# Schematic.net
KiCad netlist of a schematic drawn in Altium Designer
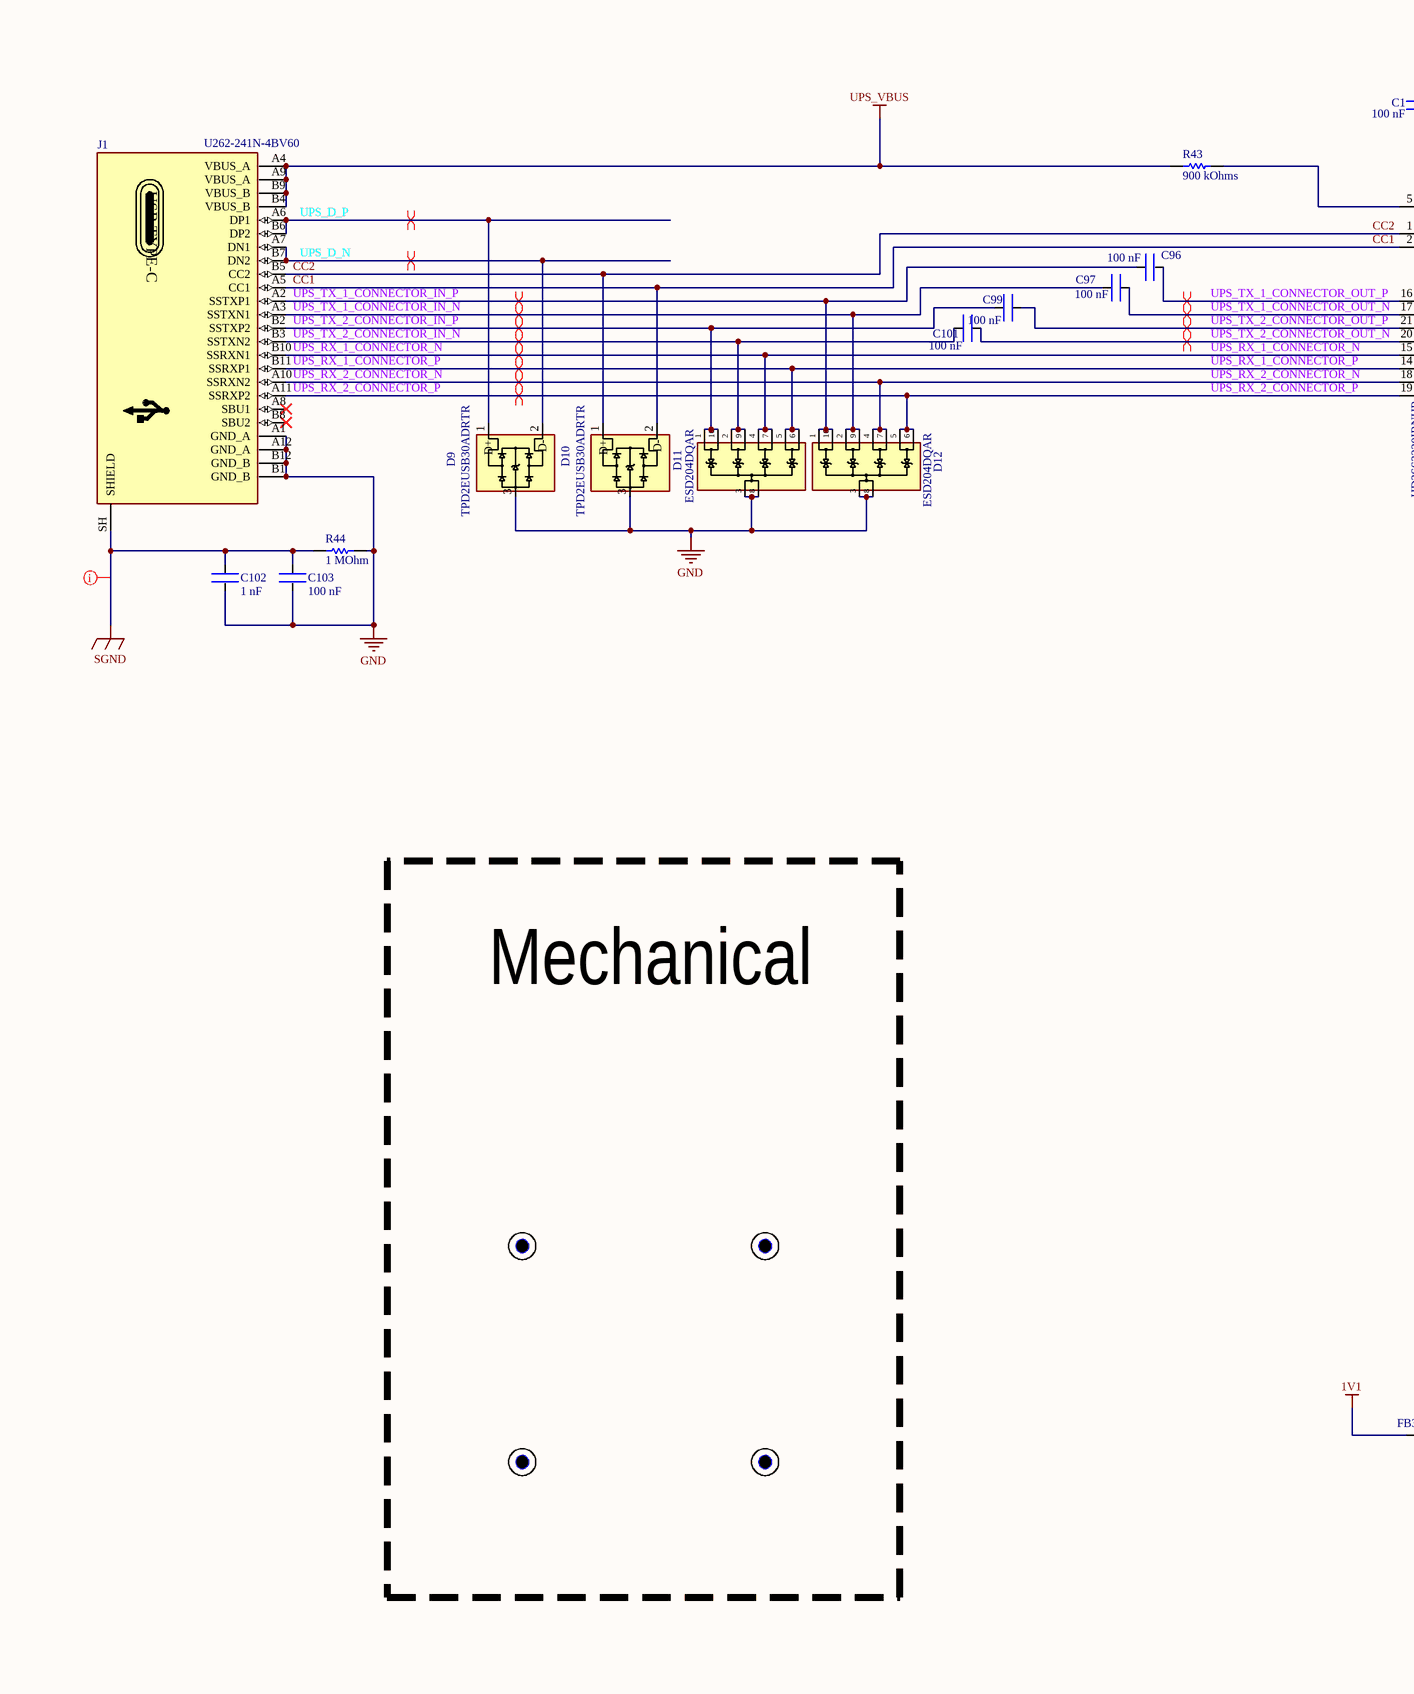
[diagram p0: Schematic.SchDoc, top left]
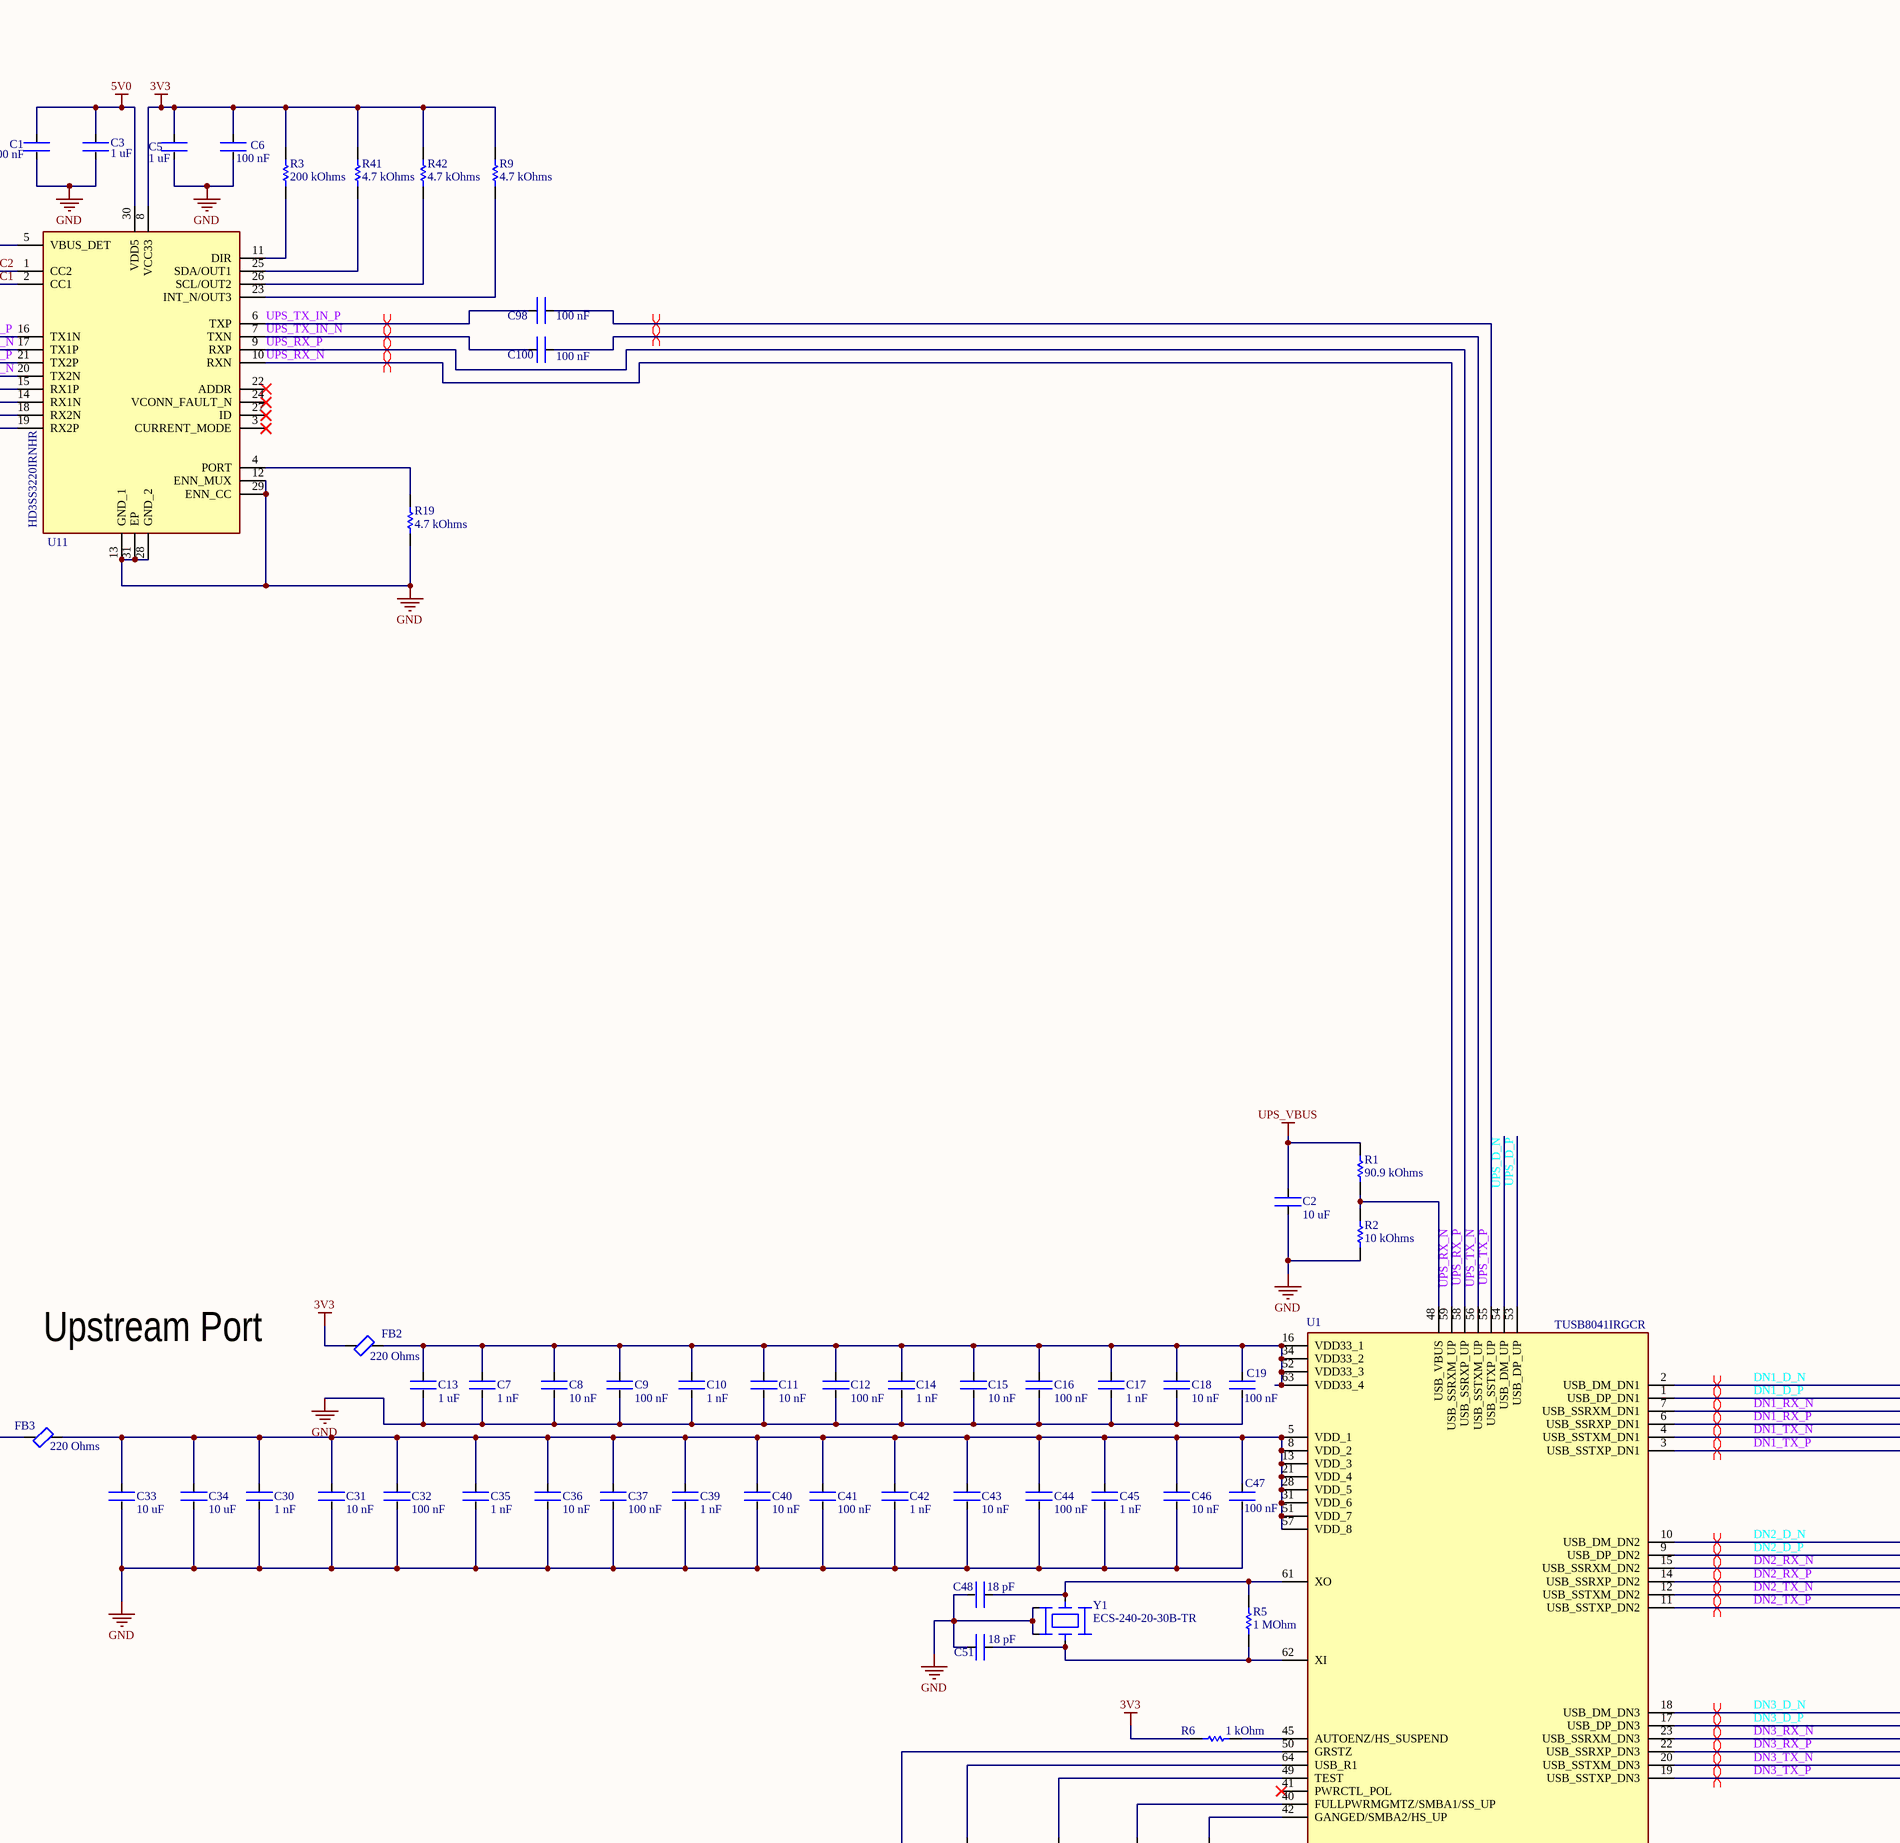
[diagram p1: Schematic.SchDoc, top middle]
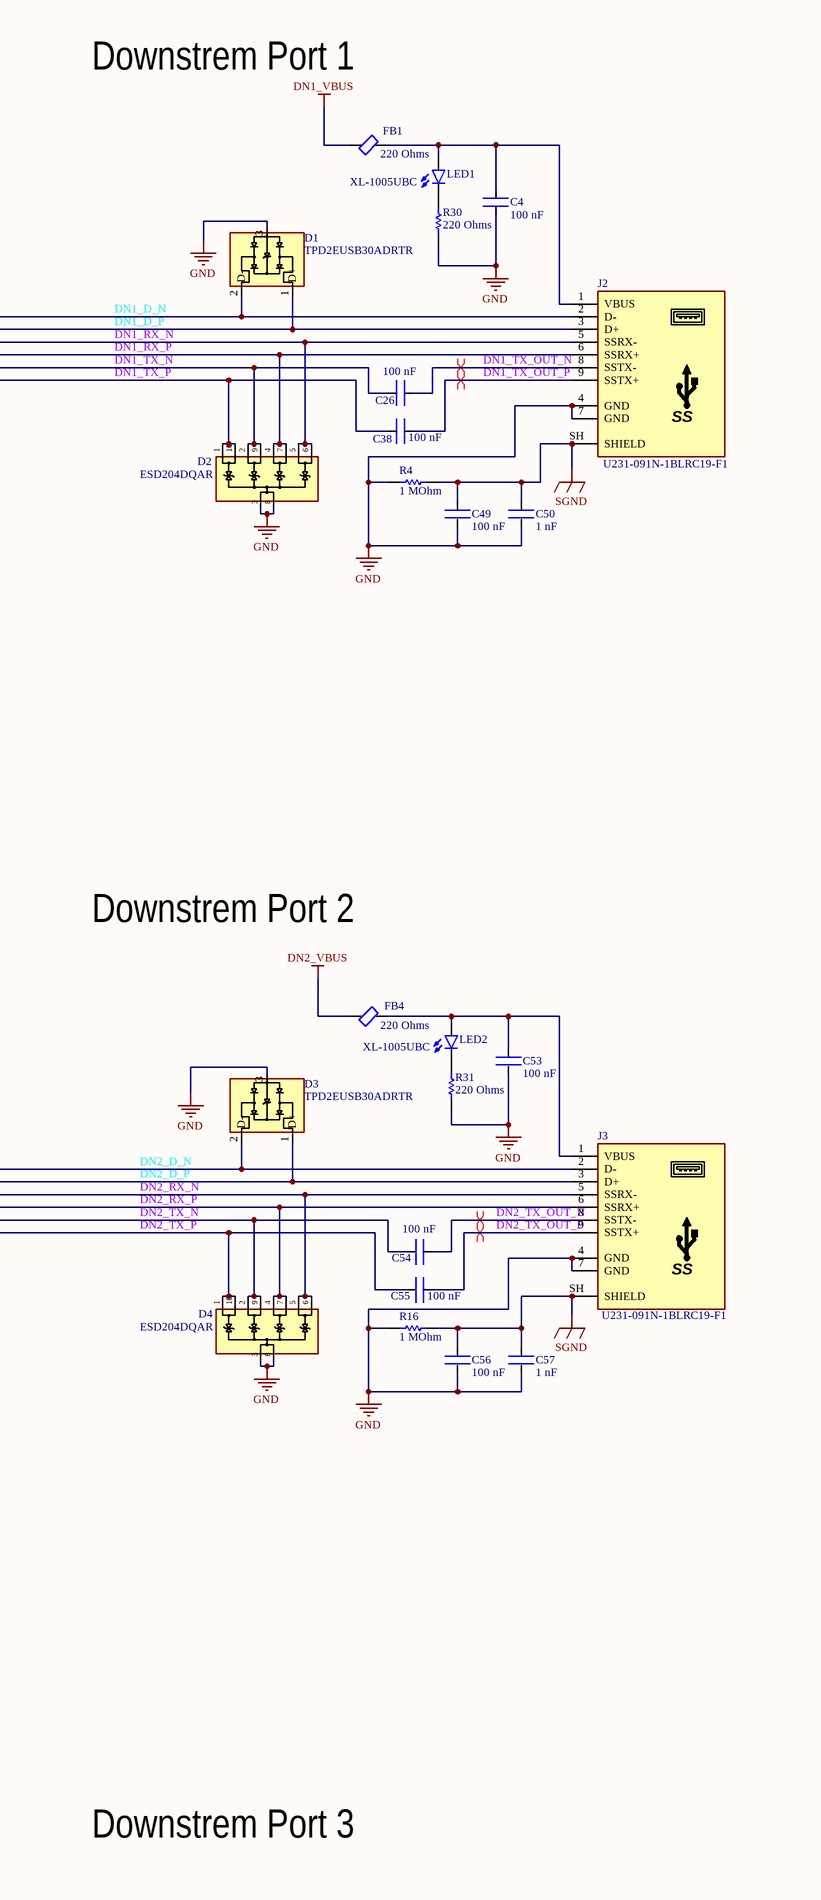
[diagram p2: Schematic.SchDoc, top right]
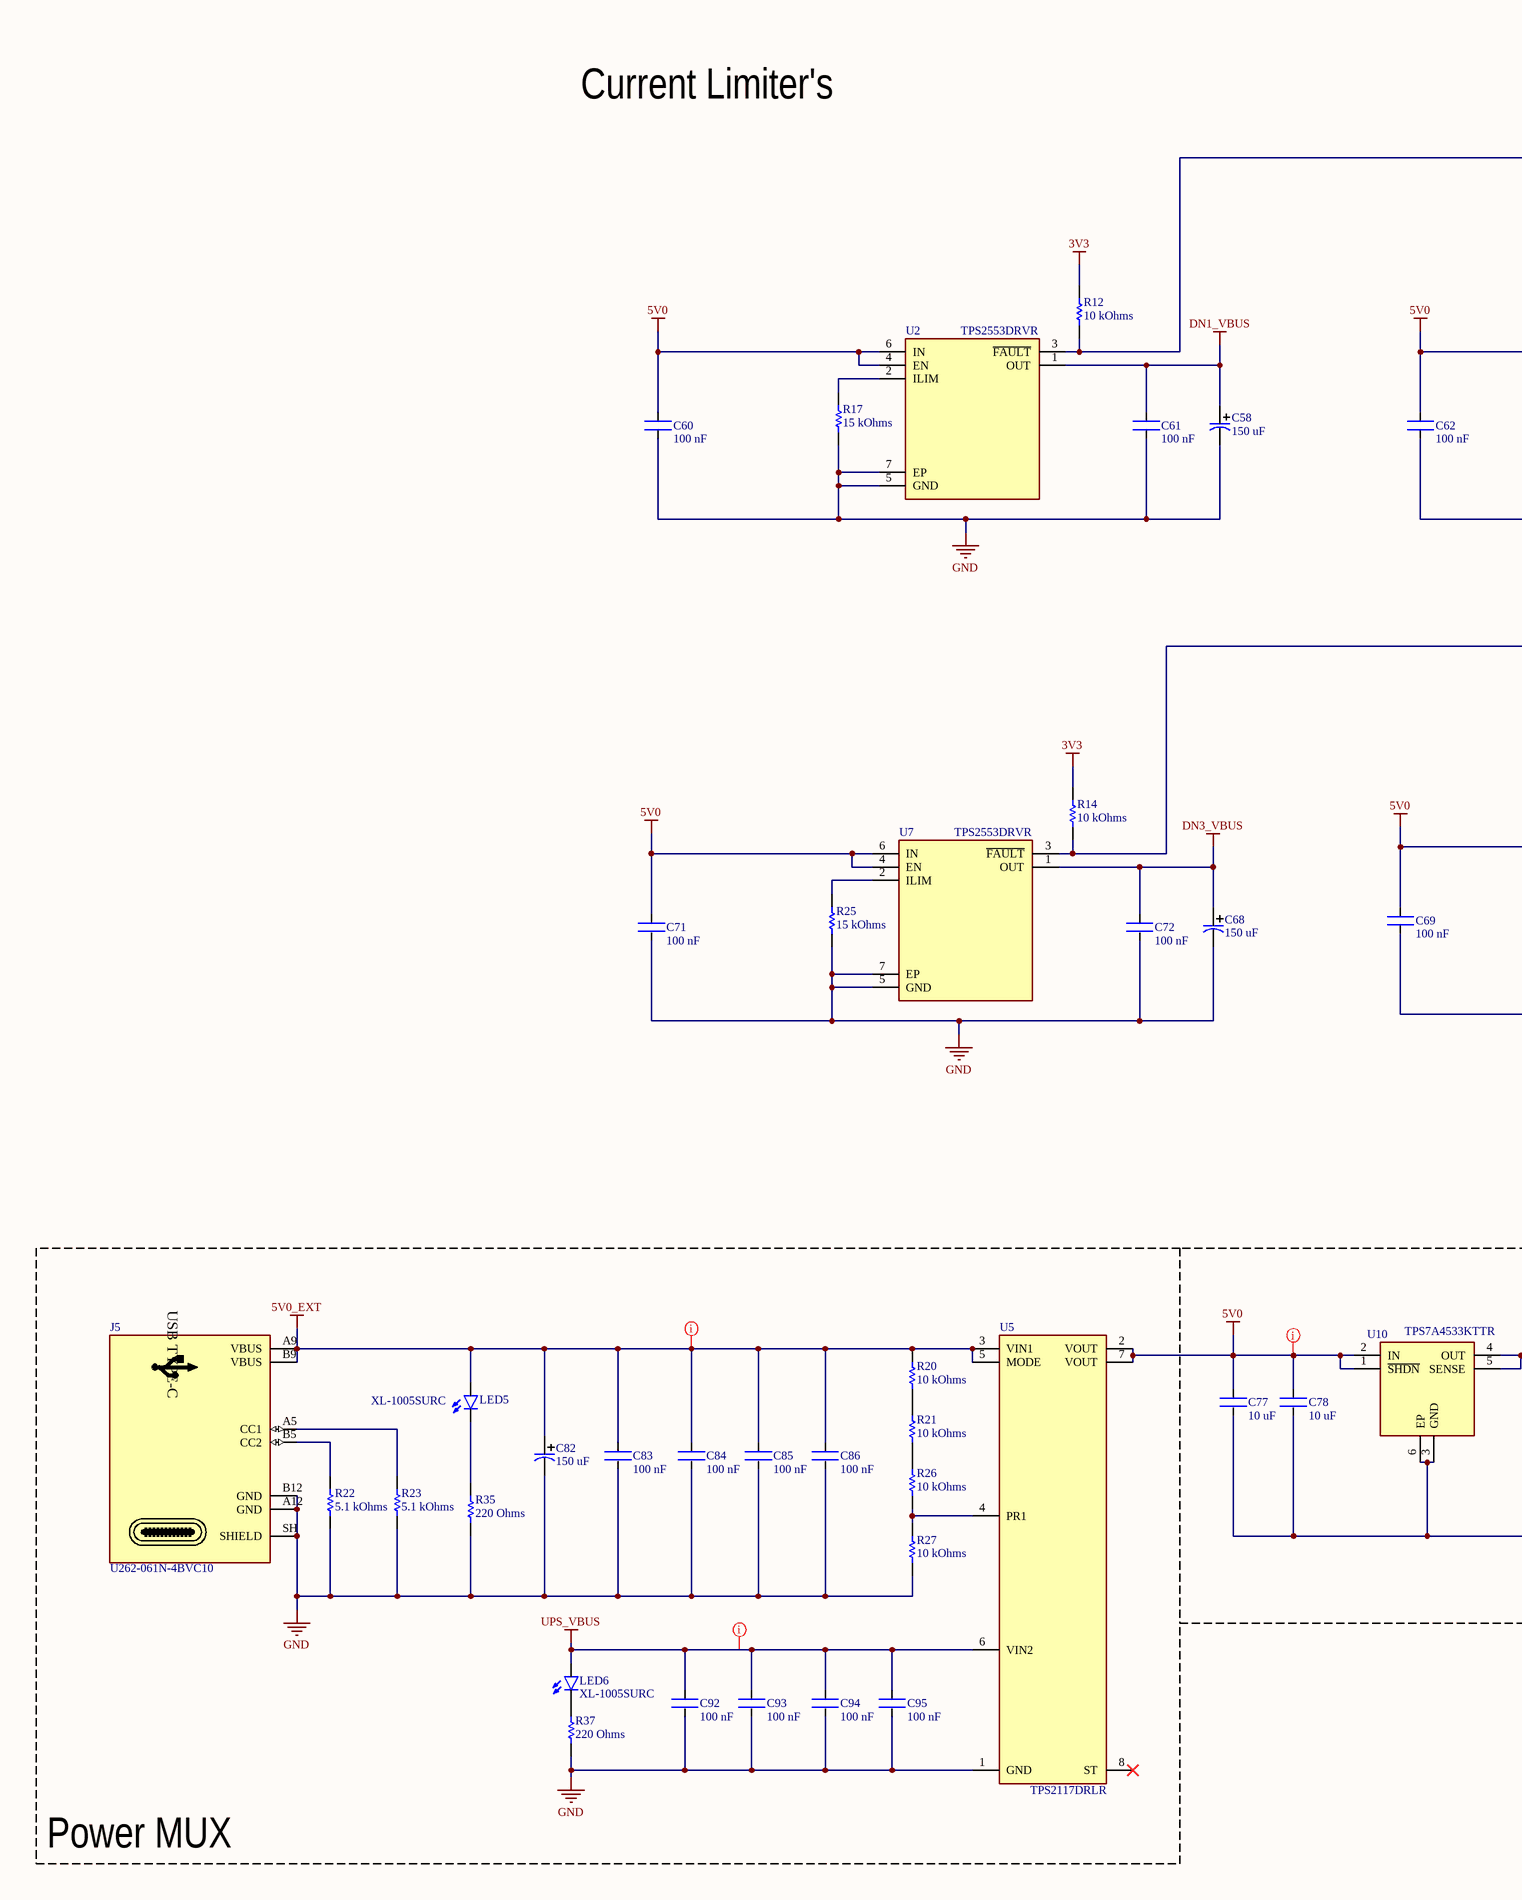
[diagram p3: Schematic.SchDoc, bottom left]
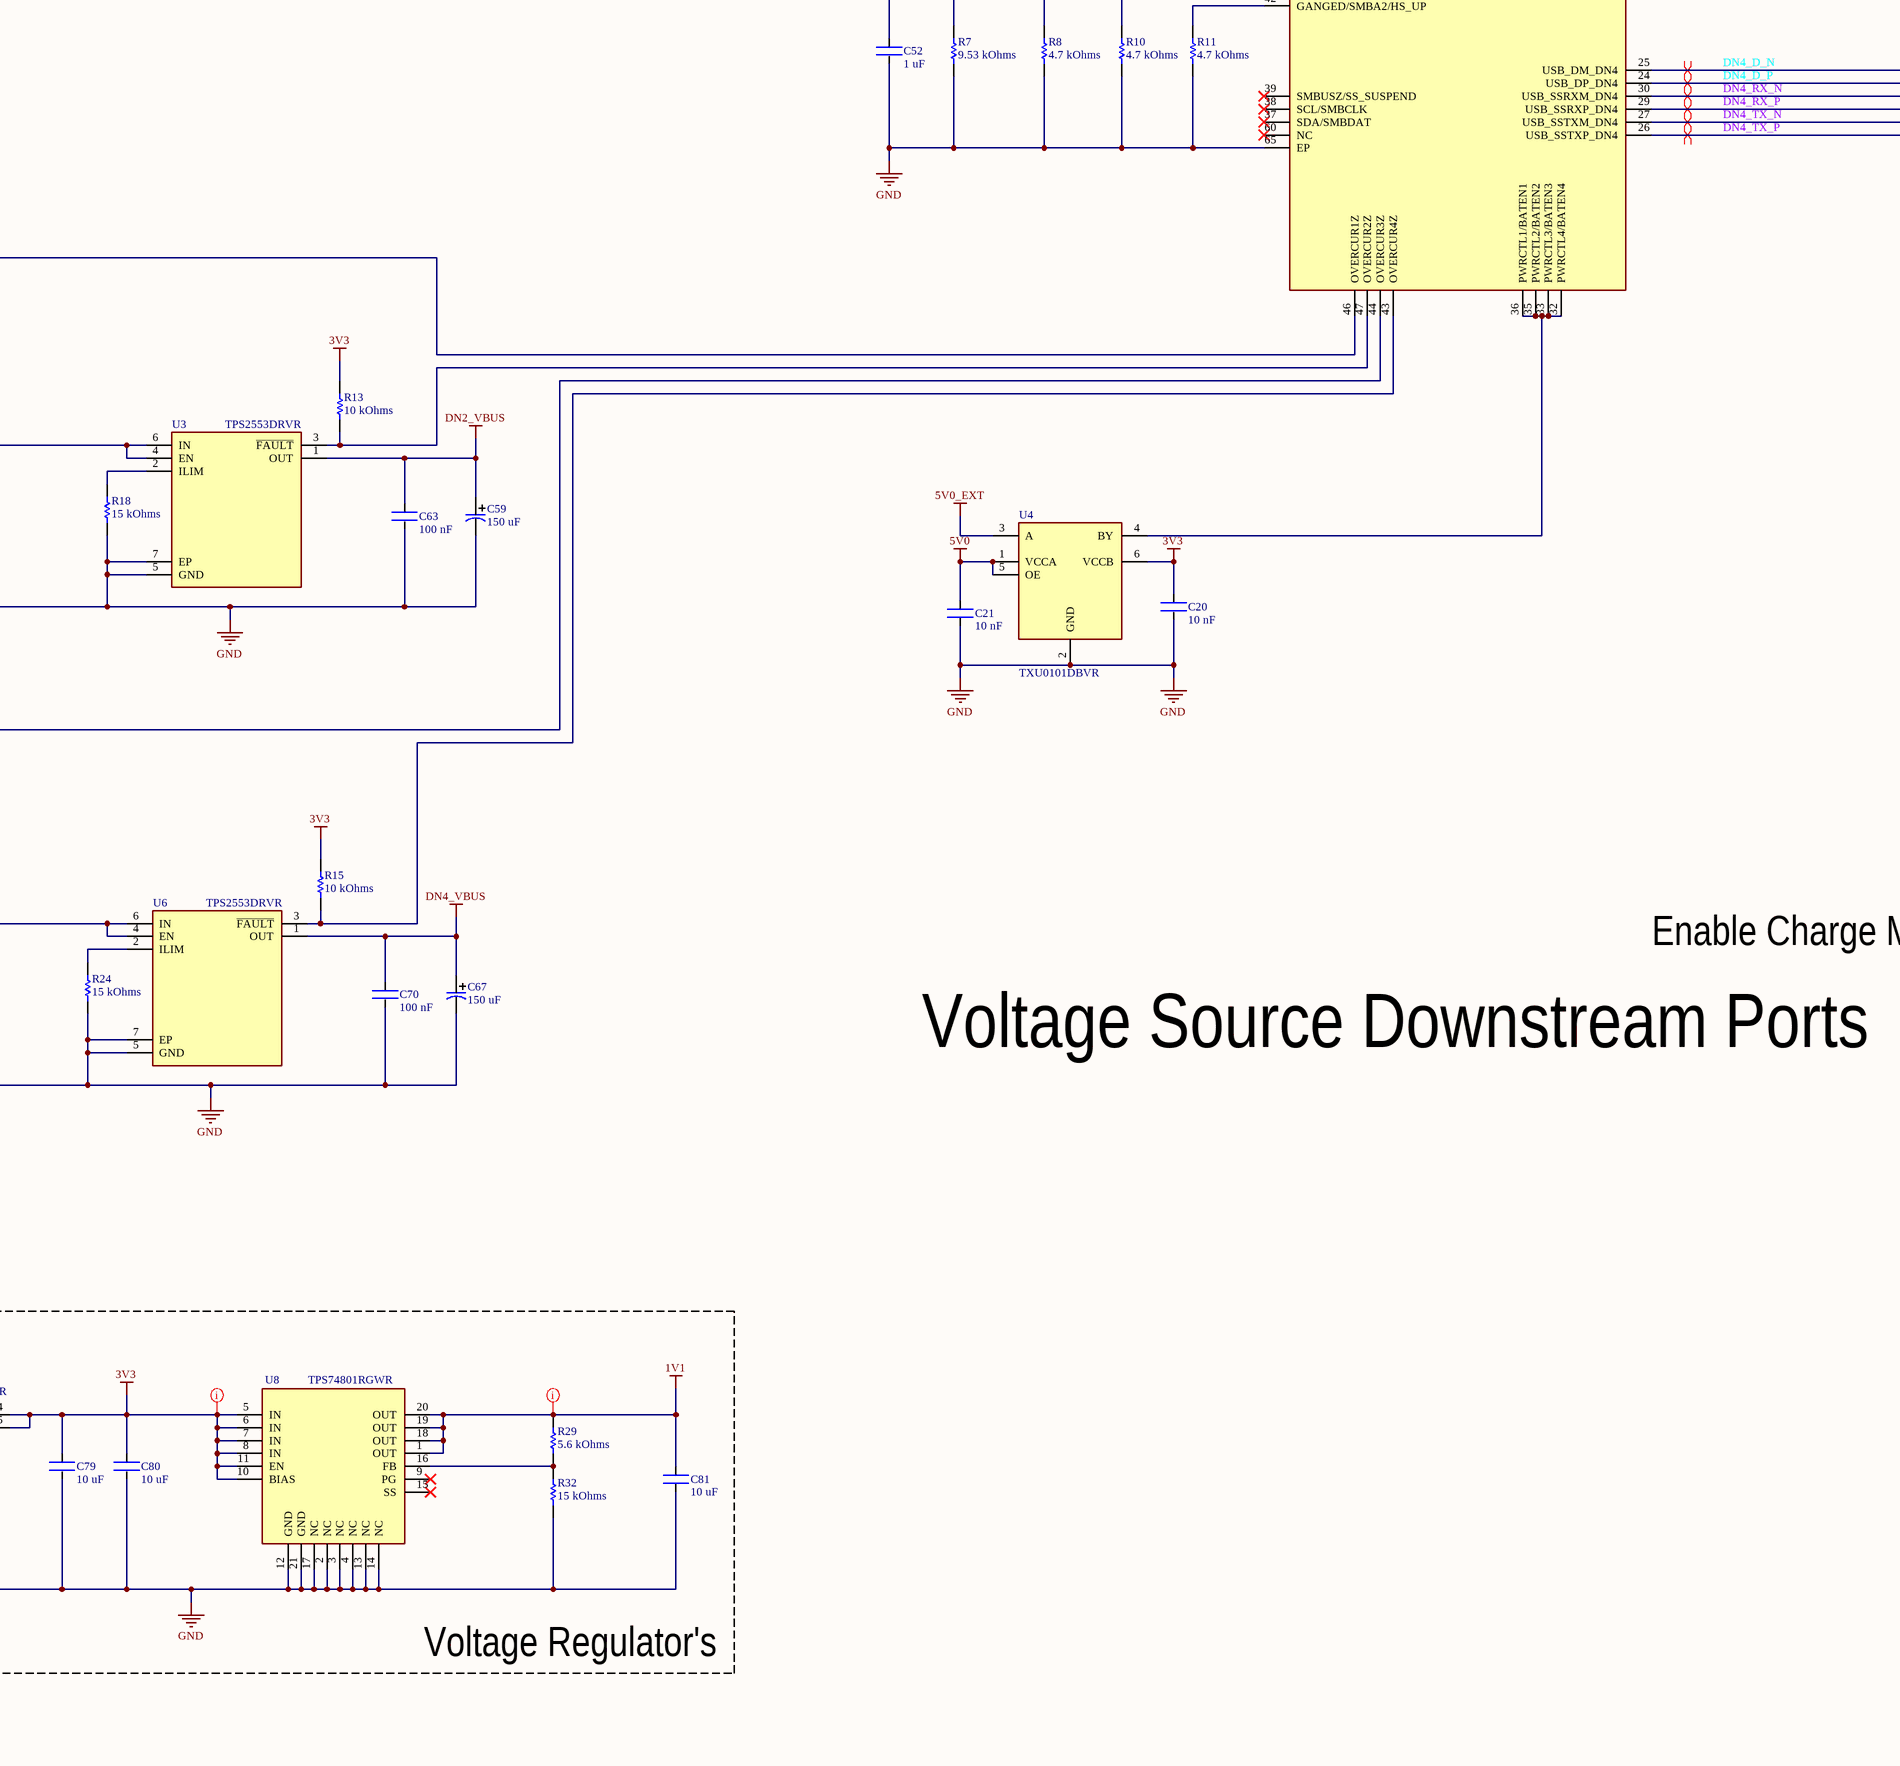
[diagram p4: Schematic.SchDoc, bottom middle]
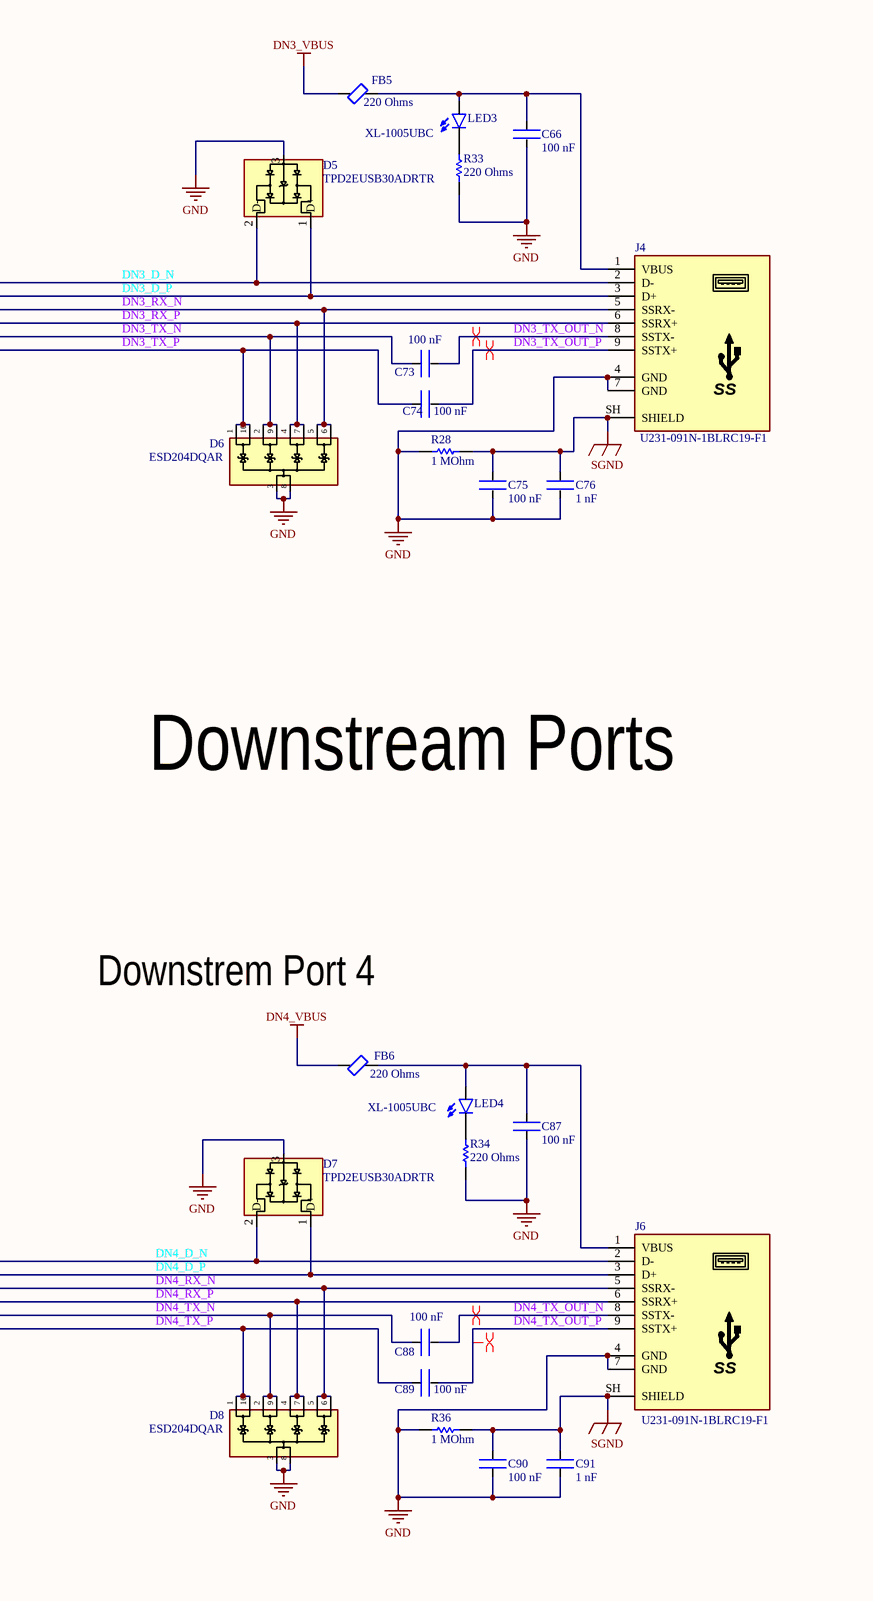
[diagram p5: Schematic.SchDoc, bottom right]

(export (version "E")
  (design (tool "Eeschema 10.0.6"))
  (components
    (comp (ref "1")
      (value "Furo")
      (footprint "FURO_M2_DIN7985")
      (description "Furo para parafuso M2")
      (fields (field (name "PART NUMBER") "FURO_M2_DIN7985"))
      (libsource (lib "MemLib") (part "Furo"))
    )
    (comp (ref "2")
      (value "Furo")
      (footprint "FURO_M2_DIN7985")
      (description "Furo para parafuso M2")
      (fields (field (name "PART NUMBER") "FURO_M2_DIN7985"))
      (libsource (lib "MemLib") (part "Furo"))
    )
    (comp (ref "3")
      (value "Furo")
      (footprint "FURO_M2_DIN7985")
      (description "Furo para parafuso M2")
      (fields (field (name "PART NUMBER") "FURO_M2_DIN7985"))
      (libsource (lib "MemLib") (part "Furo"))
    )
    (comp (ref "4")
      (value "Furo")
      (footprint "FURO_M2_DIN7985")
      (description "Furo para parafuso M2")
      (fields (field (name "PART NUMBER") "FURO_M2_DIN7985"))
      (libsource (lib "MemLib") (part "Furo"))
    )
    (comp (ref "C1")
      (value "100 nF")
      (footprint "0402")
      (description "Multilayer Ceramic Capacitors MLCC - SMD/SMT 100nF+/-10% 16V X7R 0402")
      (fields (field (name "PART NUMBER") "CL05B104KO5NNNC") (field (name "Comment") "CAPNPOL"))
      (libsource (lib "MemLib") (part "CAPNPOL"))
    )
    (comp (ref "C2")
      (value "10 uF")
      (footprint "0402")
      (description "Multilayer Ceramic Capacitors MLCC - SMD/SMT 10uF+/-20% 10V X5R 1005")
      (fields (field (name "PART NUMBER") "CL05A106MP5NUNC") (field (name "Comment") "CAPNPOL"))
      (libsource (lib "MemLib") (part "CAPNPOL"))
    )
    (comp (ref "C3")
      (value "1 uF")
      (footprint "0402")
      (description "Multilayer Ceramic Capacitors MLCC - SMD/SMT 1uF+/-10% 10V X5R 10 0402")
      (fields (field (name "PART NUMBER") "CL05A105KP5NNNC") (field (name "Comment") "CAPNPOL"))
      (libsource (lib "MemLib") (part "CAPNPOL"))
    )
    (comp (ref "C4")
      (value "100 nF")
      (footprint "0402")
      (description "Multilayer Ceramic Capacitors MLCC - SMD/SMT 100nF+/-10% 16V X7R 0402")
      (fields (field (name "PART NUMBER") "CL05B104KO5NNNC") (field (name "Comment") "CAPNPOL"))
      (libsource (lib "MemLib") (part "CAPNPOL"))
    )
    (comp (ref "C5")
      (value "1 uF")
      (footprint "0402")
      (description "Multilayer Ceramic Capacitors MLCC - SMD/SMT 1uF+/-10% 10V X5R 10 0402")
      (fields (field (name "PART NUMBER") "CL05A105KP5NNNC") (field (name "Comment") "CAPNPOL"))
      (libsource (lib "MemLib") (part "CAPNPOL"))
    )
    (comp (ref "C6")
      (value "100 nF")
      (footprint "0402")
      (description "Multilayer Ceramic Capacitors MLCC - SMD/SMT 100nF+/-10% 16V X7R 0402")
      (fields (field (name "PART NUMBER") "CL05B104KO5NNNC") (field (name "Comment") "CAPNPOL"))
      (libsource (lib "MemLib") (part "CAPNPOL"))
    )
    (comp (ref "C7")
      (value "1 nF")
      (footprint "0402")
      (description "Multilayer Ceramic Capacitors MLCC - SMD/SMT 1nF+/-10% 50V X7R 1005")
      (fields (field (name "PART NUMBER") "CL05B102KB5NNNC") (field (name "Comment") "CAPNPOL"))
      (libsource (lib "MemLib") (part "CAPNPOL"))
    )
    (comp (ref "C8")
      (value "10 nF")
      (footprint "0402")
      (description "Multilayer Ceramic Capacitors MLCC - SMD/SMT 10nF+/-10% 50V X7R 1 0402")
      (fields (field (name "PART NUMBER") "CL05B103KB5NNNC") (field (name "Comment") "CAPNPOL"))
      (libsource (lib "MemLib") (part "CAPNPOL"))
    )
    (comp (ref "C9")
      (value "100 nF")
      (footprint "0402")
      (description "Multilayer Ceramic Capacitors MLCC - SMD/SMT 100nF+/-10% 16V X7R 0402")
      (fields (field (name "PART NUMBER") "CL05B104KO5NNNC") (field (name "Comment") "CAPNPOL"))
      (libsource (lib "MemLib") (part "CAPNPOL"))
    )
    (comp (ref "C10")
      (value "1 nF")
      (footprint "0402")
      (description "Multilayer Ceramic Capacitors MLCC - SMD/SMT 1nF+/-10% 50V X7R 1005")
      (fields (field (name "PART NUMBER") "CL05B102KB5NNNC") (field (name "Comment") "CAPNPOL"))
      (libsource (lib "MemLib") (part "CAPNPOL"))
    )
    (comp (ref "C11")
      (value "10 nF")
      (footprint "0402")
      (description "Multilayer Ceramic Capacitors MLCC - SMD/SMT 10nF+/-10% 50V X7R 1 0402")
      (fields (field (name "PART NUMBER") "CL05B103KB5NNNC") (field (name "Comment") "CAPNPOL"))
      (libsource (lib "MemLib") (part "CAPNPOL"))
    )
    (comp (ref "C12")
      (value "100 nF")
      (footprint "0402")
      (description "Multilayer Ceramic Capacitors MLCC - SMD/SMT 100nF+/-10% 16V X7R 0402")
      (fields (field (name "PART NUMBER") "CL05B104KO5NNNC") (field (name "Comment") "CAPNPOL"))
      (libsource (lib "MemLib") (part "CAPNPOL"))
    )
    (comp (ref "C13")
      (value "1 uF")
      (footprint "0402")
      (description "Multilayer Ceramic Capacitors MLCC - SMD/SMT 1uF+/-10% 10V X5R 10 0402")
      (fields (field (name "PART NUMBER") "CL05A105KP5NNNC") (field (name "Comment") "CAPNPOL"))
      (libsource (lib "MemLib") (part "CAPNPOL"))
    )
    (comp (ref "C14")
      (value "1 nF")
      (footprint "0402")
      (description "Multilayer Ceramic Capacitors MLCC - SMD/SMT 1nF+/-10% 50V X7R 1005")
      (fields (field (name "PART NUMBER") "CL05B102KB5NNNC") (field (name "Comment") "CAPNPOL"))
      (libsource (lib "MemLib") (part "CAPNPOL"))
    )
    (comp (ref "C15")
      (value "10 nF")
      (footprint "0402")
      (description "Multilayer Ceramic Capacitors MLCC - SMD/SMT 10nF+/-10% 50V X7R 1 0402")
      (fields (field (name "PART NUMBER") "CL05B103KB5NNNC") (field (name "Comment") "CAPNPOL"))
      (libsource (lib "MemLib") (part "CAPNPOL"))
    )
    (comp (ref "C16")
      (value "100 nF")
      (footprint "0402")
      (description "Multilayer Ceramic Capacitors MLCC - SMD/SMT 100nF+/-10% 16V X7R 0402")
      (fields (field (name "PART NUMBER") "CL05B104KO5NNNC") (field (name "Comment") "CAPNPOL"))
      (libsource (lib "MemLib") (part "CAPNPOL"))
    )
    (comp (ref "C17")
      (value "1 nF")
      (footprint "0402")
      (description "Multilayer Ceramic Capacitors MLCC - SMD/SMT 1nF+/-10% 50V X7R 1005")
      (fields (field (name "PART NUMBER") "CL05B102KB5NNNC") (field (name "Comment") "CAPNPOL"))
      (libsource (lib "MemLib") (part "CAPNPOL"))
    )
    (comp (ref "C18")
      (value "10 nF")
      (footprint "0402")
      (description "Multilayer Ceramic Capacitors MLCC - SMD/SMT 10nF+/-10% 50V X7R 1 0402")
      (fields (field (name "PART NUMBER") "CL05B103KB5NNNC") (field (name "Comment") "CAPNPOL"))
      (libsource (lib "MemLib") (part "CAPNPOL"))
    )
    (comp (ref "C19")
      (value "100 nF")
      (footprint "0402")
      (description "Multilayer Ceramic Capacitors MLCC - SMD/SMT 100nF+/-10% 16V X7R 0402")
      (fields (field (name "PART NUMBER") "CL05B104KO5NNNC") (field (name "Comment") "CAPNPOL"))
      (libsource (lib "MemLib") (part "CAPNPOL"))
    )
    (comp (ref "C20")
      (value "10 nF")
      (footprint "0402")
      (description "Multilayer Ceramic Capacitors MLCC - SMD/SMT 10nF+/-10% 50V X7R 1 0402")
      (fields (field (name "PART NUMBER") "CL05B103KB5NNNC") (field (name "Comment") "CAPNPOL"))
      (libsource (lib "MemLib") (part "CAPNPOL"))
    )
    (comp (ref "C21")
      (value "10 nF")
      (footprint "0402")
      (description "Multilayer Ceramic Capacitors MLCC - SMD/SMT 10nF+/-10% 50V X7R 1 0402")
      (fields (field (name "PART NUMBER") "CL05B103KB5NNNC") (field (name "Comment") "CAPNPOL"))
      (libsource (lib "MemLib") (part "CAPNPOL"))
    )
    (comp (ref "C26")
      (value "100 nF")
      (footprint "0201")
      (description "Multilayer Ceramic Capacitors MLCC - SMD/SMT 0.1 uF 10 VDC 10% 0201 X5R")
      (fields (field (name "PART NUMBER") "GRM033R61A104KE15D") (field (name "Comment") "CAPNPOL"))
      (libsource (lib "MemLib") (part "CAPNPOL"))
    )
    (comp (ref "C30")
      (value "1 nF")
      (footprint "0402")
      (description "Multilayer Ceramic Capacitors MLCC - SMD/SMT 1nF+/-10% 50V X7R 1005")
      (fields (field (name "PART NUMBER") "CL05B102KB5NNNC") (field (name "Comment") "CAPNPOL"))
      (libsource (lib "MemLib") (part "CAPNPOL"))
    )
    (comp (ref "C31")
      (value "10 nF")
      (footprint "0402")
      (description "Multilayer Ceramic Capacitors MLCC - SMD/SMT 10nF+/-10% 50V X7R 1 0402")
      (fields (field (name "PART NUMBER") "CL05B103KB5NNNC") (field (name "Comment") "CAPNPOL"))
      (libsource (lib "MemLib") (part "CAPNPOL"))
    )
    (comp (ref "C32")
      (value "100 nF")
      (footprint "0402")
      (description "Multilayer Ceramic Capacitors MLCC - SMD/SMT 100nF+/-10% 16V X7R 0402")
      (fields (field (name "PART NUMBER") "CL05B104KO5NNNC") (field (name "Comment") "CAPNPOL"))
      (libsource (lib "MemLib") (part "CAPNPOL"))
    )
    (comp (ref "C33")
      (value "10 uF")
      (footprint "0402")
      (description "Multilayer Ceramic Capacitors MLCC - SMD/SMT 10uF+/-20% 10V X5R 1005")
      (fields (field (name "PART NUMBER") "CL05A106MP5NUNC") (field (name "Comment") "CAPNPOL"))
      (libsource (lib "MemLib") (part "CAPNPOL"))
    )
    (comp (ref "C34")
      (value "10 uF")
      (footprint "0402")
      (description "Multilayer Ceramic Capacitors MLCC - SMD/SMT 10uF+/-20% 10V X5R 1005")
      (fields (field (name "PART NUMBER") "CL05A106MP5NUNC") (field (name "Comment") "CAPNPOL"))
      (libsource (lib "MemLib") (part "CAPNPOL"))
    )
    (comp (ref "C35")
      (value "1 nF")
      (footprint "0402")
      (description "Multilayer Ceramic Capacitors MLCC - SMD/SMT 1nF+/-10% 50V X7R 1005")
      (fields (field (name "PART NUMBER") "CL05B102KB5NNNC") (field (name "Comment") "CAPNPOL"))
      (libsource (lib "MemLib") (part "CAPNPOL"))
    )
    (comp (ref "C36")
      (value "10 nF")
      (footprint "0402")
      (description "Multilayer Ceramic Capacitors MLCC - SMD/SMT 10nF+/-10% 50V X7R 1 0402")
      (fields (field (name "PART NUMBER") "CL05B103KB5NNNC") (field (name "Comment") "CAPNPOL"))
      (libsource (lib "MemLib") (part "CAPNPOL"))
    )
    (comp (ref "C37")
      (value "100 nF")
      (footprint "0402")
      (description "Multilayer Ceramic Capacitors MLCC - SMD/SMT 100nF+/-10% 16V X7R 0402")
      (fields (field (name "PART NUMBER") "CL05B104KO5NNNC") (field (name "Comment") "CAPNPOL"))
      (libsource (lib "MemLib") (part "CAPNPOL"))
    )
    (comp (ref "C38")
      (value "100 nF")
      (footprint "0201")
      (description "Multilayer Ceramic Capacitors MLCC - SMD/SMT 0.1 uF 10 VDC 10% 0201 X5R")
      (fields (field (name "PART NUMBER") "GRM033R61A104KE15D") (field (name "Comment") "CAPNPOL"))
      (libsource (lib "MemLib") (part "CAPNPOL"))
    )
    (comp (ref "C39")
      (value "1 nF")
      (footprint "0402")
      (description "Multilayer Ceramic Capacitors MLCC - SMD/SMT 1nF+/-10% 50V X7R 1005")
      (fields (field (name "PART NUMBER") "CL05B102KB5NNNC") (field (name "Comment") "CAPNPOL"))
      (libsource (lib "MemLib") (part "CAPNPOL"))
    )
    (comp (ref "C40")
      (value "10 nF")
      (footprint "0402")
      (description "Multilayer Ceramic Capacitors MLCC - SMD/SMT 10nF+/-10% 50V X7R 1 0402")
      (fields (field (name "PART NUMBER") "CL05B103KB5NNNC") (field (name "Comment") "CAPNPOL"))
      (libsource (lib "MemLib") (part "CAPNPOL"))
    )
    (comp (ref "C41")
      (value "100 nF")
      (footprint "0402")
      (description "Multilayer Ceramic Capacitors MLCC - SMD/SMT 100nF+/-10% 16V X7R 0402")
      (fields (field (name "PART NUMBER") "CL05B104KO5NNNC") (field (name "Comment") "CAPNPOL"))
      (libsource (lib "MemLib") (part "CAPNPOL"))
    )
    (comp (ref "C42")
      (value "1 nF")
      (footprint "0402")
      (description "Multilayer Ceramic Capacitors MLCC - SMD/SMT 1nF+/-10% 50V X7R 1005")
      (fields (field (name "PART NUMBER") "CL05B102KB5NNNC") (field (name "Comment") "CAPNPOL"))
      (libsource (lib "MemLib") (part "CAPNPOL"))
    )
    (comp (ref "C43")
      (value "10 nF")
      (footprint "0402")
      (description "Multilayer Ceramic Capacitors MLCC - SMD/SMT 10nF+/-10% 50V X7R 1 0402")
      (fields (field (name "PART NUMBER") "CL05B103KB5NNNC") (field (name "Comment") "CAPNPOL"))
      (libsource (lib "MemLib") (part "CAPNPOL"))
    )
    (comp (ref "C44")
      (value "100 nF")
      (footprint "0402")
      (description "Multilayer Ceramic Capacitors MLCC - SMD/SMT 100nF+/-10% 16V X7R 0402")
      (fields (field (name "PART NUMBER") "CL05B104KO5NNNC") (field (name "Comment") "CAPNPOL"))
      (libsource (lib "MemLib") (part "CAPNPOL"))
    )
    (comp (ref "C45")
      (value "1 nF")
      (footprint "0402")
      (description "Multilayer Ceramic Capacitors MLCC - SMD/SMT 1nF+/-10% 50V X7R 1005")
      (fields (field (name "PART NUMBER") "CL05B102KB5NNNC") (field (name "Comment") "CAPNPOL"))
      (libsource (lib "MemLib") (part "CAPNPOL"))
    )
    (comp (ref "C46")
      (value "10 nF")
      (footprint "0402")
      (description "Multilayer Ceramic Capacitors MLCC - SMD/SMT 10nF+/-10% 50V X7R 1 0402")
      (fields (field (name "PART NUMBER") "CL05B103KB5NNNC") (field (name "Comment") "CAPNPOL"))
      (libsource (lib "MemLib") (part "CAPNPOL"))
    )
    (comp (ref "C47")
      (value "100 nF")
      (footprint "0402")
      (description "Multilayer Ceramic Capacitors MLCC - SMD/SMT 100nF+/-10% 16V X7R 0402")
      (fields (field (name "PART NUMBER") "CL05B104KO5NNNC") (field (name "Comment") "CAPNPOL"))
      (libsource (lib "MemLib") (part "CAPNPOL"))
    )
    (comp (ref "C48")
      (value "18 pF")
      (footprint "0402")
      (description "Multilayer Ceramic Capacitors MLCC - SMD/SMT 50 V 18 pF C0G 0402 5%")
      (fields (field (name "PART NUMBER") "CC0402JRNPO9BN180") (field (name "Comment") "CAPNPOL"))
      (libsource (lib "MemLib") (part "CAPNPOL"))
    )
    (comp (ref "C49")
      (value "100 nF")
      (footprint "0402")
      (description "Multilayer Ceramic Capacitors MLCC - SMD/SMT 100nF+/-10% 16V X7R 0402")
      (fields (field (name "PART NUMBER") "CL05B104KO5NNNC") (field (name "Comment") "CAPNPOL"))
      (libsource (lib "MemLib") (part "CAPNPOL"))
    )
    (comp (ref "C50")
      (value "1 nF")
      (footprint "0402")
      (description "Multilayer Ceramic Capacitors MLCC - SMD/SMT 1nF+/-10% 50V X7R 1005")
      (fields (field (name "PART NUMBER") "CL05B102KB5NNNC") (field (name "Comment") "CAPNPOL"))
      (libsource (lib "MemLib") (part "CAPNPOL"))
    )
    (comp (ref "C51")
      (value "18 pF")
      (footprint "0402")
      (description "Multilayer Ceramic Capacitors MLCC - SMD/SMT 50 V 18 pF C0G 0402 5%")
      (fields (field (name "PART NUMBER") "CC0402JRNPO9BN180") (field (name "Comment") "CAPNPOL"))
      (libsource (lib "MemLib") (part "CAPNPOL"))
    )
    (comp (ref "C52")
      (value "1 uF")
      (footprint "0402")
      (description "Multilayer Ceramic Capacitors MLCC - SMD/SMT 1uF+/-10% 10V X5R 10 0402")
      (fields (field (name "PART NUMBER") "CL05A105KP5NNNC") (field (name "Comment") "CAPNPOL"))
      (libsource (lib "MemLib") (part "CAPNPOL"))
    )
    (comp (ref "C53")
      (value "100 nF")
      (footprint "0402")
      (description "Multilayer Ceramic Capacitors MLCC - SMD/SMT 100nF+/-10% 16V X7R 0402")
      (fields (field (name "PART NUMBER") "CL05B104KO5NNNC") (field (name "Comment") "CAPNPOL"))
      (libsource (lib "MemLib") (part "CAPNPOL"))
    )
    (comp (ref "C54")
      (value "100 nF")
      (footprint "0201")
      (description "Multilayer Ceramic Capacitors MLCC - SMD/SMT 0.1 uF 10 VDC 10% 0201 X5R")
      (fields (field (name "PART NUMBER") "GRM033R61A104KE15D") (field (name "Comment") "CAPNPOL"))
      (libsource (lib "MemLib") (part "CAPNPOL"))
    )
    (comp (ref "C55")
      (value "100 nF")
      (footprint "0201")
      (description "Multilayer Ceramic Capacitors MLCC - SMD/SMT 0.1 uF 10 VDC 10% 0201 X5R")
      (fields (field (name "PART NUMBER") "GRM033R61A104KE15D") (field (name "Comment") "CAPNPOL"))
      (libsource (lib "MemLib") (part "CAPNPOL"))
    )
    (comp (ref "C56")
      (value "100 nF")
      (footprint "0402")
      (description "Multilayer Ceramic Capacitors MLCC - SMD/SMT 100nF+/-10% 16V X7R 0402")
      (fields (field (name "PART NUMBER") "CL05B104KO5NNNC") (field (name "Comment") "CAPNPOL"))
      (libsource (lib "MemLib") (part "CAPNPOL"))
    )
    (comp (ref "C57")
      (value "1 nF")
      (footprint "0402")
      (description "Multilayer Ceramic Capacitors MLCC - SMD/SMT 1nF+/-10% 50V X7R 1005")
      (fields (field (name "PART NUMBER") "CL05B102KB5NNNC") (field (name "Comment") "CAPNPOL"))
      (libsource (lib "MemLib") (part "CAPNPOL"))
    )
    (comp (ref "C58")
      (value "150 uF")
      (footprint "A-3216-18")
      (description "Tantalum Capacitors - Solid SMD 4V 150uF 1206 20% ESR=800mOhms")
      (fields (field (name "PART NUMBER") "T490A157M004ATE800") (field (name "Comment") "CAPPOL"))
      (libsource (lib "MemLib") (part "CAPPOL"))
    )
    (comp (ref "C59")
      (value "150 uF")
      (footprint "A-3216-18")
      (description "Tantalum Capacitors - Solid SMD 4V 150uF 1206 20% ESR=800mOhms")
      (fields (field (name "PART NUMBER") "T490A157M004ATE800") (field (name "Comment") "CAPPOL"))
      (libsource (lib "MemLib") (part "CAPPOL"))
    )
    (comp (ref "C60")
      (value "100 nF")
      (footprint "0402")
      (description "Multilayer Ceramic Capacitors MLCC - SMD/SMT 100nF+/-10% 16V X7R 0402")
      (fields (field (name "PART NUMBER") "CL05B104KO5NNNC") (field (name "Comment") "CAPNPOL"))
      (libsource (lib "MemLib") (part "CAPNPOL"))
    )
    (comp (ref "C61")
      (value "100 nF")
      (footprint "0402")
      (description "Multilayer Ceramic Capacitors MLCC - SMD/SMT 100nF+/-10% 16V X7R 0402")
      (fields (field (name "PART NUMBER") "CL05B104KO5NNNC") (field (name "Comment") "CAPNPOL"))
      (libsource (lib "MemLib") (part "CAPNPOL"))
    )
    (comp (ref "C62")
      (value "100 nF")
      (footprint "0402")
      (description "Multilayer Ceramic Capacitors MLCC - SMD/SMT 100nF+/-10% 16V X7R 0402")
      (fields (field (name "PART NUMBER") "CL05B104KO5NNNC") (field (name "Comment") "CAPNPOL"))
      (libsource (lib "MemLib") (part "CAPNPOL"))
    )
    (comp (ref "C63")
      (value "100 nF")
      (footprint "0402")
      (description "Multilayer Ceramic Capacitors MLCC - SMD/SMT 100nF+/-10% 16V X7R 0402")
      (fields (field (name "PART NUMBER") "CL05B104KO5NNNC") (field (name "Comment") "CAPNPOL"))
      (libsource (lib "MemLib") (part "CAPNPOL"))
    )
    (comp (ref "C66")
      (value "100 nF")
      (footprint "0402")
      (description "Multilayer Ceramic Capacitors MLCC - SMD/SMT 100nF+/-10% 16V X7R 0402")
      (fields (field (name "PART NUMBER") "CL05B104KO5NNNC") (field (name "Comment") "CAPNPOL"))
      (libsource (lib "MemLib") (part "CAPNPOL"))
    )
    (comp (ref "C67")
      (value "150 uF")
      (footprint "A-3216-18")
      (description "Tantalum Capacitors - Solid SMD 4V 150uF 1206 20% ESR=800mOhms")
      (fields (field (name "PART NUMBER") "T490A157M004ATE800") (field (name "Comment") "CAPPOL"))
      (libsource (lib "MemLib") (part "CAPPOL"))
    )
    (comp (ref "C68")
      (value "150 uF")
      (footprint "A-3216-18")
      (description "Tantalum Capacitors - Solid SMD 4V 150uF 1206 20% ESR=800mOhms")
      (fields (field (name "PART NUMBER") "T490A157M004ATE800") (field (name "Comment") "CAPPOL"))
      (libsource (lib "MemLib") (part "CAPPOL"))
    )
    (comp (ref "C69")
      (value "100 nF")
      (footprint "0402")
      (description "Multilayer Ceramic Capacitors MLCC - SMD/SMT 100nF+/-10% 16V X7R 0402")
      (fields (field (name "PART NUMBER") "CL05B104KO5NNNC") (field (name "Comment") "CAPNPOL"))
      (libsource (lib "MemLib") (part "CAPNPOL"))
    )
    (comp (ref "C70")
      (value "100 nF")
      (footprint "0402")
      (description "Multilayer Ceramic Capacitors MLCC - SMD/SMT 100nF+/-10% 16V X7R 0402")
      (fields (field (name "PART NUMBER") "CL05B104KO5NNNC") (field (name "Comment") "CAPNPOL"))
      (libsource (lib "MemLib") (part "CAPNPOL"))
    )
    (comp (ref "C71")
      (value "100 nF")
      (footprint "0402")
      (description "Multilayer Ceramic Capacitors MLCC - SMD/SMT 100nF+/-10% 16V X7R 0402")
      (fields (field (name "PART NUMBER") "CL05B104KO5NNNC") (field (name "Comment") "CAPNPOL"))
      (libsource (lib "MemLib") (part "CAPNPOL"))
    )
    (comp (ref "C72")
      (value "100 nF")
      (footprint "0402")
      (description "Multilayer Ceramic Capacitors MLCC - SMD/SMT 100nF+/-10% 16V X7R 0402")
      (fields (field (name "PART NUMBER") "CL05B104KO5NNNC") (field (name "Comment") "CAPNPOL"))
      (libsource (lib "MemLib") (part "CAPNPOL"))
    )
    (comp (ref "C73")
      (value "100 nF")
      (footprint "0201")
      (description "Multilayer Ceramic Capacitors MLCC - SMD/SMT 0.1 uF 10 VDC 10% 0201 X5R")
      (fields (field (name "PART NUMBER") "GRM033R61A104KE15D") (field (name "Comment") "CAPNPOL"))
      (libsource (lib "MemLib") (part "CAPNPOL"))
    )
    (comp (ref "C74")
      (value "100 nF")
      (footprint "0201")
      (description "Multilayer Ceramic Capacitors MLCC - SMD/SMT 0.1 uF 10 VDC 10% 0201 X5R")
      (fields (field (name "PART NUMBER") "GRM033R61A104KE15D") (field (name "Comment") "CAPNPOL"))
      (libsource (lib "MemLib") (part "CAPNPOL"))
    )
    (comp (ref "C75")
      (value "100 nF")
      (footprint "0402")
      (description "Multilayer Ceramic Capacitors MLCC - SMD/SMT 100nF+/-10% 16V X7R 0402")
      (fields (field (name "PART NUMBER") "CL05B104KO5NNNC") (field (name "Comment") "CAPNPOL"))
      (libsource (lib "MemLib") (part "CAPNPOL"))
    )
    (comp (ref "C76")
      (value "1 nF")
      (footprint "0402")
      (description "Multilayer Ceramic Capacitors MLCC - SMD/SMT 1nF+/-10% 50V X7R 1005")
      (fields (field (name "PART NUMBER") "CL05B102KB5NNNC") (field (name "Comment") "CAPNPOL"))
      (libsource (lib "MemLib") (part "CAPNPOL"))
    )
    (comp (ref "C77")
      (value "10 uF")
      (footprint "0402")
      (description "Multilayer Ceramic Capacitors MLCC - SMD/SMT 10uF+/-20% 10V X5R 1005")
      (fields (field (name "PART NUMBER") "CL05A106MP5NUNC") (field (name "Comment") "CAPNPOL"))
      (libsource (lib "MemLib") (part "CAPNPOL"))
    )
    (comp (ref "C78")
      (value "10 uF")
      (footprint "0402")
      (description "Multilayer Ceramic Capacitors MLCC - SMD/SMT 10uF+/-20% 10V X5R 1005")
      (fields (field (name "PART NUMBER") "CL05A106MP5NUNC") (field (name "Comment") "CAPNPOL"))
      (libsource (lib "MemLib") (part "CAPNPOL"))
    )
    (comp (ref "C79")
      (value "10 uF")
      (footprint "0402")
      (description "Multilayer Ceramic Capacitors MLCC - SMD/SMT 10uF+/-20% 10V X5R 1005")
      (fields (field (name "PART NUMBER") "CL05A106MP5NUNC") (field (name "Comment") "CAPNPOL"))
      (libsource (lib "MemLib") (part "CAPNPOL"))
    )
    (comp (ref "C80")
      (value "10 uF")
      (footprint "0402")
      (description "Multilayer Ceramic Capacitors MLCC - SMD/SMT 10uF+/-20% 10V X5R 1005")
      (fields (field (name "PART NUMBER") "CL05A106MP5NUNC") (field (name "Comment") "CAPNPOL"))
      (libsource (lib "MemLib") (part "CAPNPOL"))
    )
    (comp (ref "C81")
      (value "10 uF")
      (footprint "0402")
      (description "Multilayer Ceramic Capacitors MLCC - SMD/SMT 10uF+/-20% 10V X5R 1005")
      (fields (field (name "PART NUMBER") "CL05A106MP5NUNC") (field (name "Comment") "CAPNPOL"))
      (libsource (lib "MemLib") (part "CAPNPOL"))
    )
    (comp (ref "C82")
      (value "150 uF")
      (footprint "A-3216-18")
      (description "Tantalum Capacitors - Solid SMD 4V 150uF 1206 20% ESR=800mOhms")
      (fields (field (name "PART NUMBER") "T490A157M004ATE800") (field (name "Comment") "CAPPOL"))
      (libsource (lib "MemLib") (part "CAPPOL"))
    )
    (comp (ref "C83")
      (value "100 nF")
      (footprint "0402")
      (description "Multilayer Ceramic Capacitors MLCC - SMD/SMT 100nF+/-10% 16V X7R 0402")
      (fields (field (name "PART NUMBER") "CL05B104KO5NNNC") (field (name "Comment") "CAPNPOL"))
      (libsource (lib "MemLib") (part "CAPNPOL"))
    )
    (comp (ref "C84")
      (value "100 nF")
      (footprint "0402")
      (description "Multilayer Ceramic Capacitors MLCC - SMD/SMT 100nF+/-10% 16V X7R 0402")
      (fields (field (name "PART NUMBER") "CL05B104KO5NNNC") (field (name "Comment") "CAPNPOL"))
      (libsource (lib "MemLib") (part "CAPNPOL"))
    )
    (comp (ref "C85")
      (value "100 nF")
      (footprint "0402")
      (description "Multilayer Ceramic Capacitors MLCC - SMD/SMT 100nF+/-10% 16V X7R 0402")
      (fields (field (name "PART NUMBER") "CL05B104KO5NNNC") (field (name "Comment") "CAPNPOL"))
      (libsource (lib "MemLib") (part "CAPNPOL"))
    )
    (comp (ref "C86")
      (value "100 nF")
      (footprint "0402")
      (description "Multilayer Ceramic Capacitors MLCC - SMD/SMT 100nF+/-10% 16V X7R 0402")
      (fields (field (name "PART NUMBER") "CL05B104KO5NNNC") (field (name "Comment") "CAPNPOL"))
      (libsource (lib "MemLib") (part "CAPNPOL"))
    )
    (comp (ref "C87")
      (value "100 nF")
      (footprint "0402")
      (description "Multilayer Ceramic Capacitors MLCC - SMD/SMT 100nF+/-10% 16V X7R 0402")
      (fields (field (name "PART NUMBER") "CL05B104KO5NNNC") (field (name "Comment") "CAPNPOL"))
      (libsource (lib "MemLib") (part "CAPNPOL"))
    )
    (comp (ref "C88")
      (value "100 nF")
      (footprint "0201")
      (description "Multilayer Ceramic Capacitors MLCC - SMD/SMT 0.1 uF 10 VDC 10% 0201 X5R")
      (fields (field (name "PART NUMBER") "GRM033R61A104KE15D") (field (name "Comment") "CAPNPOL"))
      (libsource (lib "MemLib") (part "CAPNPOL"))
    )
    (comp (ref "C89")
      (value "100 nF")
      (footprint "0201")
      (description "Multilayer Ceramic Capacitors MLCC - SMD/SMT 0.1 uF 10 VDC 10% 0201 X5R")
      (fields (field (name "PART NUMBER") "GRM033R61A104KE15D") (field (name "Comment") "CAPNPOL"))
      (libsource (lib "MemLib") (part "CAPNPOL"))
    )
    (comp (ref "C90")
      (value "100 nF")
      (footprint "0402")
      (description "Multilayer Ceramic Capacitors MLCC - SMD/SMT 100nF+/-10% 16V X7R 0402")
      (fields (field (name "PART NUMBER") "CL05B104KO5NNNC") (field (name "Comment") "CAPNPOL"))
      (libsource (lib "MemLib") (part "CAPNPOL"))
    )
    (comp (ref "C91")
      (value "1 nF")
      (footprint "0402")
      (description "Multilayer Ceramic Capacitors MLCC - SMD/SMT 1nF+/-10% 50V X7R 1005")
      (fields (field (name "PART NUMBER") "CL05B102KB5NNNC") (field (name "Comment") "CAPNPOL"))
      (libsource (lib "MemLib") (part "CAPNPOL"))
    )
    (comp (ref "C92")
      (value "100 nF")
      (footprint "0402")
      (description "Multilayer Ceramic Capacitors MLCC - SMD/SMT 100nF+/-10% 16V X7R 0402")
      (fields (field (name "PART NUMBER") "CL05B104KO5NNNC") (field (name "Comment") "CAPNPOL"))
      (libsource (lib "MemLib") (part "CAPNPOL"))
    )
    (comp (ref "C93")
      (value "100 nF")
      (footprint "0402")
      (description "Multilayer Ceramic Capacitors MLCC - SMD/SMT 100nF+/-10% 16V X7R 0402")
      (fields (field (name "PART NUMBER") "CL05B104KO5NNNC") (field (name "Comment") "CAPNPOL"))
      (libsource (lib "MemLib") (part "CAPNPOL"))
    )
    (comp (ref "C94")
      (value "100 nF")
      (footprint "0402")
      (description "Multilayer Ceramic Capacitors MLCC - SMD/SMT 100nF+/-10% 16V X7R 0402")
      (fields (field (name "PART NUMBER") "CL05B104KO5NNNC") (field (name "Comment") "CAPNPOL"))
      (libsource (lib "MemLib") (part "CAPNPOL"))
    )
    (comp (ref "C95")
      (value "100 nF")
      (footprint "0402")
      (description "Multilayer Ceramic Capacitors MLCC - SMD/SMT 100nF+/-10% 16V X7R 0402")
      (fields (field (name "PART NUMBER") "CL05B104KO5NNNC") (field (name "Comment") "CAPNPOL"))
      (libsource (lib "MemLib") (part "CAPNPOL"))
    )
    (comp (ref "C96")
      (value "100 nF")
      (footprint "0201")
      (description "Multilayer Ceramic Capacitors MLCC - SMD/SMT 0.1 uF 10 VDC 10% 0201 X5R")
      (fields (field (name "PART NUMBER") "GRM033R61A104KE15D") (field (name "Comment") "CAPNPOL"))
      (libsource (lib "MemLib") (part "CAPNPOL"))
    )
    (comp (ref "C97")
      (value "100 nF")
      (footprint "0201")
      (description "Multilayer Ceramic Capacitors MLCC - SMD/SMT 0.1 uF 10 VDC 10% 0201 X5R")
      (fields (field (name "PART NUMBER") "GRM033R61A104KE15D") (field (name "Comment") "CAPNPOL"))
      (libsource (lib "MemLib") (part "CAPNPOL"))
    )
    (comp (ref "C98")
      (value "100 nF")
      (footprint "0201")
      (description "Multilayer Ceramic Capacitors MLCC - SMD/SMT 0.1 uF 10 VDC 10% 0201 X5R")
      (fields (field (name "PART NUMBER") "GRM033R61A104KE15D") (field (name "Comment") "CAPNPOL"))
      (libsource (lib "MemLib") (part "CAPNPOL"))
    )
    (comp (ref "C99")
      (value "100 nF")
      (footprint "0201")
      (description "Multilayer Ceramic Capacitors MLCC - SMD/SMT 0.1 uF 10 VDC 10% 0201 X5R")
      (fields (field (name "PART NUMBER") "GRM033R61A104KE15D") (field (name "Comment") "CAPNPOL"))
      (libsource (lib "MemLib") (part "CAPNPOL"))
    )
    (comp (ref "C100")
      (value "100 nF")
      (footprint "0201")
      (description "Multilayer Ceramic Capacitors MLCC - SMD/SMT 0.1 uF 10 VDC 10% 0201 X5R")
      (fields (field (name "PART NUMBER") "GRM033R61A104KE15D") (field (name "Comment") "CAPNPOL"))
      (libsource (lib "MemLib") (part "CAPNPOL"))
    )
    (comp (ref "C101")
      (value "100 nF")
      (footprint "0201")
      (description "Multilayer Ceramic Capacitors MLCC - SMD/SMT 0.1 uF 10 VDC 10% 0201 X5R")
      (fields (field (name "PART NUMBER") "GRM033R61A104KE15D") (field (name "Comment") "CAPNPOL"))
      (libsource (lib "MemLib") (part "CAPNPOL"))
    )
    (comp (ref "C102")
      (value "1 nF")
      (footprint "0402")
      (description "Multilayer Ceramic Capacitors MLCC - SMD/SMT 1nF+/-10% 50V X7R 1005")
      (fields (field (name "PART NUMBER") "CL05B102KB5NNNC") (field (name "Comment") "CAPNPOL"))
      (libsource (lib "MemLib") (part "CAPNPOL"))
    )
    (comp (ref "C103")
      (value "100 nF")
      (footprint "0402")
      (description "Multilayer Ceramic Capacitors MLCC - SMD/SMT 100nF+/-10% 16V X7R 0402")
      (fields (field (name "PART NUMBER") "CL05B104KO5NNNC") (field (name "Comment") "CAPNPOL"))
      (libsource (lib "MemLib") (part "CAPNPOL"))
    )
    (comp (ref "D1")
      (value "TPD2EUSB30")
      (footprint "DRT_(R-PDSO-N3)")
      (description "ESD Protection Diodes / TVS Diodes 2 Channel ESD/ Surge Solution")
      (fields (field (name "PART NUMBER") "TPD2EUSB30ADRTR") (field (name "NOME") "TPD2EUSB30ADRTR"))
      (libsource (lib "MemLib") (part "TPD2EUSB30"))
    )
    (comp (ref "D2")
      (value "ESD204DQAR")
      (footprint "DQA0010A")
      (description "ESD Protection Diodes / TVS Diodes Quad 0.55-pF +/-3.6 -V +/-30-kV ESD pro")
      (fields (field (name "NOME") "ESD204DQAR"))
      (libsource (lib "MemLib") (part "ESD204DQAR"))
    )
    (comp (ref "D3")
      (value "TPD2EUSB30")
      (footprint "DRT_(R-PDSO-N3)")
      (description "ESD Protection Diodes / TVS Diodes 2 Channel ESD/ Surge Solution")
      (fields (field (name "PART NUMBER") "TPD2EUSB30ADRTR") (field (name "NOME") "TPD2EUSB30ADRTR"))
      (libsource (lib "MemLib") (part "TPD2EUSB30"))
    )
    (comp (ref "D4")
      (value "ESD204DQAR")
      (footprint "DQA0010A")
      (description "ESD Protection Diodes / TVS Diodes Quad 0.55-pF +/-3.6 -V +/-30-kV ESD pro")
      (fields (field (name "NOME") "ESD204DQAR"))
      (libsource (lib "MemLib") (part "ESD204DQAR"))
    )
    (comp (ref "D5")
      (value "TPD2EUSB30")
      (footprint "DRT_(R-PDSO-N3)")
      (description "ESD Protection Diodes / TVS Diodes 2 Channel ESD/ Surge Solution")
      (fields (field (name "PART NUMBER") "TPD2EUSB30ADRTR") (field (name "NOME") "TPD2EUSB30ADRTR"))
      (libsource (lib "MemLib") (part "TPD2EUSB30"))
    )
    (comp (ref "D6")
      (value "ESD204DQAR")
      (footprint "DQA0010A")
      (description "ESD Protection Diodes / TVS Diodes Quad 0.55-pF +/-3.6 -V +/-30-kV ESD pro")
      (fields (field (name "NOME") "ESD204DQAR"))
      (libsource (lib "MemLib") (part "ESD204DQAR"))
    )
    (comp (ref "D7")
      (value "TPD2EUSB30")
      (footprint "DRT_(R-PDSO-N3)")
      (description "ESD Protection Diodes / TVS Diodes 2 Channel ESD/ Surge Solution")
      (fields (field (name "PART NUMBER") "TPD2EUSB30ADRTR") (field (name "NOME") "TPD2EUSB30ADRTR"))
      (libsource (lib "MemLib") (part "TPD2EUSB30"))
    )
    (comp (ref "D8")
      (value "ESD204DQAR")
      (footprint "DQA0010A")
      (description "ESD Protection Diodes / TVS Diodes Quad 0.55-pF +/-3.6 -V +/-30-kV ESD pro")
      (fields (field (name "NOME") "ESD204DQAR"))
      (libsource (lib "MemLib") (part "ESD204DQAR"))
    )
    (comp (ref "D9")
      (value "TPD2EUSB30")
      (footprint "DRT_(R-PDSO-N3)")
      (description "ESD Protection Diodes / TVS Diodes 2 Channel ESD/ Surge Solution")
      (fields (field (name "PART NUMBER") "TPD2EUSB30ADRTR") (field (name "NOME") "TPD2EUSB30ADRTR"))
      (libsource (lib "") (part "TPD2EUSB30_1"))
    )
    (comp (ref "D10")
      (value "TPD2EUSB30")
      (footprint "DRT_(R-PDSO-N3)")
      (description "ESD Protection Diodes / TVS Diodes 2 Channel ESD/ Surge Solution")
      (fields (field (name "PART NUMBER") "TPD2EUSB30ADRTR") (field (name "NOME") "TPD2EUSB30ADRTR"))
      (libsource (lib "") (part "TPD2EUSB30_1"))
    )
    (comp (ref "D11")
      (value "ESD204DQAR")
      (footprint "DQA0010A")
      (description "ESD Protection Diodes / TVS Diodes Quad 0.55-pF +/-3.6 -V +/-30-kV ESD pro")
      (fields (field (name "NOME") "ESD204DQAR"))
      (libsource (lib "MemLib") (part "ESD204DQAR"))
    )
    (comp (ref "D12")
      (value "ESD204DQAR")
      (footprint "DQA0010A")
      (description "ESD Protection Diodes / TVS Diodes Quad 0.55-pF +/-3.6 -V +/-30-kV ESD pro")
      (fields (field (name "NOME") "ESD204DQAR"))
      (libsource (lib "MemLib") (part "ESD204DQAR"))
    )
    (comp (ref "FB1")
      (value "FerriteBead")
      (footprint "FB0603")
      (description "Ferrite Beads 220 OHM Alternate Sizing Guide Below")
      (fields (field (name "PART NUMBER") "BLM18KG221SH1D") (field (name "IMEPDANCIA") "220 Ohms"))
      (libsource (lib "MemLib") (part "FerriteBead"))
    )
    (comp (ref "FB2")
      (value "FerriteBead")
      (footprint "FB0603")
      (description "Ferrite Beads 220 OHM Alternate Sizing Guide Below")
      (fields (field (name "PART NUMBER") "BLM18KG221SH1D") (field (name "IMEPDANCIA") "220 Ohms"))
      (libsource (lib "MemLib") (part "FerriteBead"))
    )
    (comp (ref "FB3")
      (value "FerriteBead")
      (footprint "FB0603")
      (description "Ferrite Beads 220 OHM Alternate Sizing Guide Below")
      (fields (field (name "PART NUMBER") "BLM18KG221SH1D") (field (name "IMEPDANCIA") "220 Ohms"))
      (libsource (lib "MemLib") (part "FerriteBead"))
    )
    (comp (ref "FB4")
      (value "FerriteBead")
      (footprint "FB0603")
      (description "Ferrite Beads 220 OHM Alternate Sizing Guide Below")
      (fields (field (name "PART NUMBER") "BLM18KG221SH1D") (field (name "IMEPDANCIA") "220 Ohms"))
      (libsource (lib "MemLib") (part "FerriteBead"))
    )
    (comp (ref "FB5")
      (value "FerriteBead")
      (footprint "FB0603")
      (description "Ferrite Beads 220 OHM Alternate Sizing Guide Below")
      (fields (field (name "PART NUMBER") "BLM18KG221SH1D") (field (name "IMEPDANCIA") "220 Ohms"))
      (libsource (lib "MemLib") (part "FerriteBead"))
    )
    (comp (ref "FB6")
      (value "FerriteBead")
      (footprint "FB0603")
      (description "Ferrite Beads 220 OHM Alternate Sizing Guide Below")
      (fields (field (name "PART NUMBER") "BLM18KG221SH1D") (field (name "IMEPDANCIA") "220 Ohms"))
      (libsource (lib "MemLib") (part "FerriteBead"))
    )
    (comp (ref "J1")
      (value "U262-241N-4BV60")
      (footprint "U262-241N-4BV60")
      (description "USB-C (USB TYPE-C) Receptacle Connector 24 Position Surface Mount")
      (fields (field (name "NOME") "U262-241N-4BV60"))
      (libsource (lib "MemLib") (part "U262-241N-4BV60"))
    )
    (comp (ref "J2")
      (value "U231-091N-1BLRC19-F1")
      (footprint "U231-091N-1BLRC19-F1")
      (description "USB-A (USB TYPE-A) Receptacle Connector 9 Position Through Hole")
      (fields (field (name "NOME") "U231-091N-1BLRC19-F1"))
      (libsource (lib "MemLib") (part "U231-091N-1BLRC19-F1"))
    )
    (comp (ref "J3")
      (value "U231-091N-1BLRC19-F1")
      (footprint "U231-091N-1BLRC19-F1")
      (description "USB-A (USB TYPE-A) Receptacle Connector 9 Position Through Hole")
      (fields (field (name "NOME") "U231-091N-1BLRC19-F1"))
      (libsource (lib "MemLib") (part "U231-091N-1BLRC19-F1"))
    )
    (comp (ref "J4")
      (value "U231-091N-1BLRC19-F1")
      (footprint "U231-091N-1BLRC19-F1")
      (description "USB-A (USB TYPE-A) Receptacle Connector 9 Position Through Hole")
      (fields (field (name "NOME") "U231-091N-1BLRC19-F1"))
      (libsource (lib "MemLib") (part "U231-091N-1BLRC19-F1"))
    )
    (comp (ref "J5")
      (value "U262-061N-4BVC10")
      (footprint "U262-061N-4BVC10")
      (description "USB-C (USB TYPE-C) Receptacle Connector 6 Position Surface Mount")
      (fields (field (name "NOME") "U262-061N-4BVC10"))
      (libsource (lib "MemLib") (part "U262-061N-4BVC10"))
    )
    (comp (ref "J6")
      (value "U231-091N-1BLRC19-F1")
      (footprint "U231-091N-1BLRC19-F1")
      (description "USB-A (USB TYPE-A) Receptacle Connector 9 Position Through Hole")
      (fields (field (name "NOME") "U231-091N-1BLRC19-F1"))
      (libsource (lib "MemLib") (part "U231-091N-1BLRC19-F1"))
    )
    (comp (ref "LED1")
      (value "LED")
      (footprint "0402")
      (description "LED BLUE WATER CLEAR 0402 SMD")
      (fields (field (name "PART NUMBER") "XL-1005UBC") (field (name "NOME") "XL-1005UBC"))
      (libsource (lib "MemLib") (part "LED"))
    )
    (comp (ref "LED2")
      (value "LED")
      (footprint "0402")
      (description "LED BLUE WATER CLEAR 0402 SMD")
      (fields (field (name "PART NUMBER") "XL-1005UBC") (field (name "NOME") "XL-1005UBC"))
      (libsource (lib "MemLib") (part "LED"))
    )
    (comp (ref "LED3")
      (value "LED")
      (footprint "0402")
      (description "LED BLUE WATER CLEAR 0402 SMD")
      (fields (field (name "PART NUMBER") "XL-1005UBC") (field (name "NOME") "XL-1005UBC"))
      (libsource (lib "MemLib") (part "LED"))
    )
    (comp (ref "LED4")
      (value "LED")
      (footprint "0402")
      (description "LED BLUE WATER CLEAR 0402 SMD")
      (fields (field (name "PART NUMBER") "XL-1005UBC") (field (name "NOME") "XL-1005UBC"))
      (libsource (lib "MemLib") (part "LED"))
    )
    (comp (ref "LED5")
      (value "LED")
      (footprint "0402")
      (description "Red 625nm LED Indication - Discrete 1.8V~2.4V 0402")
      (fields (field (name "PART NUMBER") "XL-1005SURC") (field (name "NOME") "XL-1005SURC"))
      (libsource (lib "MemLib") (part "LED"))
    )
    (comp (ref "LED6")
      (value "LED")
      (footprint "0402")
      (description "Red 625nm LED Indication - Discrete 1.8V~2.4V 0402")
      (fields (field (name "PART NUMBER") "XL-1005SURC") (field (name "NOME") "XL-1005SURC"))
      (libsource (lib "MemLib") (part "LED"))
    )
    (comp (ref "R1")
      (value "90.9 kOhms")
      (footprint "R0402")
      (description "Thick Film Resistors - SMD General Purpose Chip Resistor 0402, 90.9kOhms, 1%, 1/16W")
      (fields (field (name "PART NUMBER") "RC0402FR-0790K9L") (field (name "Comment") "Resistor"))
      (libsource (lib "MemLib") (part "Resistor"))
    )
    (comp (ref "R2")
      (value "10 kOhms")
      (footprint "R0402")
      (description "Thick Film Resistors - SMD General Purpose Chip Resistor 0402, 10kOhms, 1%, 1/16W")
      (fields (field (name "PART NUMBER") "RC0402FR-0710KL") (field (name "Comment") "Resistor"))
      (libsource (lib "MemLib") (part "Resistor"))
    )
    (comp (ref "R3")
      (value "200 kOhms")
      (footprint "R0402")
      (description "Thick Film Resistors - SMD General Purpose Chip Resistor 0402, 200kOhms, 1%, 1/16W")
      (fields (field (name "PART NUMBER") "RC0402FR-07200KL") (field (name "Comment") "Resistor"))
      (libsource (lib "MemLib") (part "Resistor"))
    )
    (comp (ref "R4")
      (value "1 MOhm")
      (footprint "R0402")
      (description "Thick Film Resistors - SMD General Purpose Chip Resistor 0402, 1MOhms, 1%, 1/16W")
      (fields (field (name "PART NUMBER") "RC0402FR-071ML") (field (name "Comment") "Resistor"))
      (libsource (lib "MemLib") (part "Resistor"))
    )
    (comp (ref "R5")
      (value "1 MOhm")
      (footprint "R0402")
      (description "Thick Film Resistors - SMD General Purpose Chip Resistor 0402, 1MOhms, 1%, 1/16W")
      (fields (field (name "PART NUMBER") "RC0402FR-071ML") (field (name "Comment") "Resistor"))
      (libsource (lib "MemLib") (part "Resistor"))
    )
    (comp (ref "R6")
      (value "1 kOhm")
      (footprint "R0402")
      (description "Thick Film Resistors - SMD General Purpose Chip Resistor 0402, 1kOhms, 5%, 1/16W")
      (fields (field (name "PART NUMBER") "RC0402JR-071KL") (field (name "Comment") "Resistor"))
      (libsource (lib "MemLib") (part "Resistor"))
    )
    (comp (ref "R7")
      (value "9.53 kOhms")
      (footprint "R0402")
      (description "Resistores de Filme Fino - SMD 9.53 kOhms 62.5mW 04 02 1%")
      (fields (field (name "PART NUMBER") "RC0402FR-079K53L") (field (name "Comment") "Resistor"))
      (libsource (lib "MemLib") (part "Resistor"))
    )
    (comp (ref "R8")
      (value "4.7 kOhms")
      (footprint "R0402")
      (description "Thick Film Resistors - SMD General Purpose Chip Resistor 0402, 4.7kOhms, 1%, 1/16W")
      (fields (field (name "PART NUMBER") "RC0402FR-074K7L") (field (name "Comment") "Resistor"))
      (libsource (lib "MemLib") (part "Resistor"))
    )
    (comp (ref "R9")
      (value "4.7 kOhms")
      (footprint "R0402")
      (description "Thick Film Resistors - SMD General Purpose Chip Resistor 0402, 4.7kOhms, 1%, 1/16W")
      (fields (field (name "PART NUMBER") "RC0402FR-074K7L") (field (name "Comment") "Resistor"))
      (libsource (lib "MemLib") (part "Resistor"))
    )
    (comp (ref "R10")
      (value "4.7 kOhms")
      (footprint "R0402")
      (description "Thick Film Resistors - SMD General Purpose Chip Resistor 0402, 4.7kOhms, 1%, 1/16W")
      (fields (field (name "PART NUMBER") "RC0402FR-074K7L") (field (name "Comment") "Resistor"))
      (libsource (lib "MemLib") (part "Resistor"))
    )
    (comp (ref "R11")
      (value "4.7 kOhms")
      (footprint "R0402")
      (description "Thick Film Resistors - SMD General Purpose Chip Resistor 0402, 4.7kOhms, 1%, 1/16W")
      (fields (field (name "PART NUMBER") "RC0402FR-074K7L") (field (name "Comment") "Resistor"))
      (libsource (lib "MemLib") (part "Resistor"))
    )
    (comp (ref "R12")
      (value "10 kOhms")
      (footprint "R0402")
      (description "Thick Film Resistors - SMD General Purpose Chip Resistor 0402, 10kOhms, 1%, 1/16W")
      (fields (field (name "PART NUMBER") "RC0402FR-0710KL") (field (name "Comment") "Resistor"))
      (libsource (lib "MemLib") (part "Resistor"))
    )
    (comp (ref "R13")
      (value "10 kOhms")
      (footprint "R0402")
      (description "Thick Film Resistors - SMD General Purpose Chip Resistor 0402, 10kOhms, 1%, 1/16W")
      (fields (field (name "PART NUMBER") "RC0402FR-0710KL") (field (name "Comment") "Resistor"))
      (libsource (lib "MemLib") (part "Resistor"))
    )
    (comp (ref "R14")
      (value "10 kOhms")
      (footprint "R0402")
      (description "Thick Film Resistors - SMD General Purpose Chip Resistor 0402, 10kOhms, 1%, 1/16W")
      (fields (field (name "PART NUMBER") "RC0402FR-0710KL") (field (name "Comment") "Resistor"))
      (libsource (lib "MemLib") (part "Resistor"))
    )
    (comp (ref "R15")
      (value "10 kOhms")
      (footprint "R0402")
      (description "Thick Film Resistors - SMD General Purpose Chip Resistor 0402, 10kOhms, 1%, 1/16W")
      (fields (field (name "PART NUMBER") "RC0402FR-0710KL") (field (name "Comment") "Resistor"))
      (libsource (lib "MemLib") (part "Resistor"))
    )
    (comp (ref "R16")
      (value "1 MOhm")
      (footprint "R0402")
      (description "Thick Film Resistors - SMD General Purpose Chip Resistor 0402, 1MOhms, 1%, 1/16W")
      (fields (field (name "PART NUMBER") "RC0402FR-071ML") (field (name "Comment") "Resistor"))
      (libsource (lib "MemLib") (part "Resistor"))
    )
    (comp (ref "R17")
      (value "15 kOhms")
      (footprint "R0402")
      (description "Thick Film Resistors - SMD General Purpose Chip Resistor 0402, 15kOhms, 1%, 1/16W")
      (fields (field (name "PART NUMBER") "RC0402FR-0715KL") (field (name "Comment") "Resistor"))
      (libsource (lib "MemLib") (part "Resistor"))
    )
    (comp (ref "R18")
      (value "15 kOhms")
      (footprint "R0402")
      (description "Thick Film Resistors - SMD General Purpose Chip Resistor 0402, 15kOhms, 1%, 1/16W")
      (fields (field (name "PART NUMBER") "RC0402FR-0715KL") (field (name "Comment") "Resistor"))
      (libsource (lib "MemLib") (part "Resistor"))
    )
    (comp (ref "R19")
      (value "4.7 kOhms")
      (footprint "R0402")
      (description "Thick Film Resistors - SMD General Purpose Chip Resistor 0402, 4.7kOhms, 1%, 1/16W")
      (fields (field (name "PART NUMBER") "RC0402FR-074K7L") (field (name "Comment") "Resistor"))
      (libsource (lib "MemLib") (part "Resistor"))
    )
    (comp (ref "R20")
      (value "10 kOhms")
      (footprint "R0402")
      (description "Thick Film Resistors - SMD General Purpose Chip Resistor 0402, 10kOhms, 1%, 1/16W")
      (fields (field (name "PART NUMBER") "RC0402FR-0710KL") (field (name "Comment") "Resistor"))
      (libsource (lib "MemLib") (part "Resistor"))
    )
    (comp (ref "R21")
      (value "10 kOhms")
      (footprint "R0402")
      (description "Thick Film Resistors - SMD General Purpose Chip Resistor 0402, 10kOhms, 1%, 1/16W")
      (fields (field (name "PART NUMBER") "RC0402FR-0710KL") (field (name "Comment") "Resistor"))
      (libsource (lib "MemLib") (part "Resistor"))
    )
    (comp (ref "R22")
      (value "5.1 kOhms")
      (footprint "R0402")
      (description "Thick Film Resistors - SMD General Purpose Chip Resistor 0402, 5.1kOhms, 1%, 1/16W")
      (fields (field (name "PART NUMBER") "RC0402FR-075K1L") (field (name "Comment") "Resistor"))
      (libsource (lib "MemLib") (part "Resistor"))
    )
    (comp (ref "R23")
      (value "5.1 kOhms")
      (footprint "R0402")
      (description "Thick Film Resistors - SMD General Purpose Chip Resistor 0402, 5.1kOhms, 1%, 1/16W")
      (fields (field (name "PART NUMBER") "RC0402FR-075K1L") (field (name "Comment") "Resistor"))
      (libsource (lib "MemLib") (part "Resistor"))
    )
    (comp (ref "R24")
      (value "15 kOhms")
      (footprint "R0402")
      (description "Thick Film Resistors - SMD General Purpose Chip Resistor 0402, 15kOhms, 1%, 1/16W")
      (fields (field (name "PART NUMBER") "RC0402FR-0715KL") (field (name "Comment") "Resistor"))
      (libsource (lib "MemLib") (part "Resistor"))
    )
    (comp (ref "R25")
      (value "15 kOhms")
      (footprint "R0402")
      (description "Thick Film Resistors - SMD General Purpose Chip Resistor 0402, 15kOhms, 1%, 1/16W")
      (fields (field (name "PART NUMBER") "RC0402FR-0715KL") (field (name "Comment") "Resistor"))
      (libsource (lib "MemLib") (part "Resistor"))
    )
    (comp (ref "R26")
      (value "10 kOhms")
      (footprint "R0402")
      (description "Thick Film Resistors - SMD General Purpose Chip Resistor 0402, 10kOhms, 1%, 1/16W")
      (fields (field (name "PART NUMBER") "RC0402FR-0710KL") (field (name "Comment") "Resistor"))
      (libsource (lib "MemLib") (part "Resistor"))
    )
    (comp (ref "R27")
      (value "10 kOhms")
      (footprint "R0402")
      (description "Thick Film Resistors - SMD General Purpose Chip Resistor 0402, 10kOhms, 1%, 1/16W")
      (fields (field (name "PART NUMBER") "RC0402FR-0710KL") (field (name "Comment") "Resistor"))
      (libsource (lib "MemLib") (part "Resistor"))
    )
    (comp (ref "R28")
      (value "1 MOhm")
      (footprint "R0402")
      (description "Thick Film Resistors - SMD General Purpose Chip Resistor 0402, 1MOhms, 1%, 1/16W")
      (fields (field (name "PART NUMBER") "RC0402FR-071ML") (field (name "Comment") "Resistor"))
      (libsource (lib "MemLib") (part "Resistor"))
    )
    (comp (ref "R29")
      (value "5.6 kOhms")
      (footprint "R0402")
      (description "Thick Film Resistors - SMD General Purpose Chip Resistor 0402, 5.6kOhms, 1%, 1/16W")
      (fields (field (name "PART NUMBER") "RC0402FR-075K6L") (field (name "Comment") "Resistor"))
      (libsource (lib "MemLib") (part "Resistor"))
    )
    (comp (ref "R30")
      (value "220 Ohms")
      (footprint "R0402")
      (description "Thick Film Resistors - SMD General Purpose Chip Resistor 0402, 220Ohms, 1%, 1/16W")
      (fields (field (name "PART NUMBER") "RC0402FR-07220RL") (field (name "Comment") "Resistor"))
      (libsource (lib "MemLib") (part "Resistor"))
    )
    (comp (ref "R31")
      (value "220 Ohms")
      (footprint "R0402")
      (description "Thick Film Resistors - SMD General Purpose Chip Resistor 0402, 220Ohms, 1%, 1/16W")
      (fields (field (name "PART NUMBER") "RC0402FR-07220RL") (field (name "Comment") "Resistor"))
      (libsource (lib "MemLib") (part "Resistor"))
    )
    (comp (ref "R32")
      (value "15 kOhms")
      (footprint "R0402")
      (description "Thick Film Resistors - SMD General Purpose Chip Resistor 0402, 15kOhms, 1%, 1/16W")
      (fields (field (name "PART NUMBER") "RC0402FR-0715KL") (field (name "Comment") "Resistor"))
      (libsource (lib "MemLib") (part "Resistor"))
    )
    (comp (ref "R33")
      (value "220 Ohms")
      (footprint "R0402")
      (description "Thick Film Resistors - SMD General Purpose Chip Resistor 0402, 220Ohms, 1%, 1/16W")
      (fields (field (name "PART NUMBER") "RC0402FR-07220RL") (field (name "Comment") "Resistor"))
      (libsource (lib "MemLib") (part "Resistor"))
    )
    (comp (ref "R34")
      (value "220 Ohms")
      (footprint "R0402")
      (description "Thick Film Resistors - SMD General Purpose Chip Resistor 0402, 220Ohms, 1%, 1/16W")
      (fields (field (name "PART NUMBER") "RC0402FR-07220RL") (field (name "Comment") "Resistor"))
      (libsource (lib "MemLib") (part "Resistor"))
    )
    (comp (ref "R35")
      (value "220 Ohms")
      (footprint "R0402")
      (description "Thick Film Resistors - SMD General Purpose Chip Resistor 0402, 220Ohms, 1%, 1/16W")
      (fields (field (name "PART NUMBER") "RC0402FR-07220RL") (field (name "Comment") "Resistor"))
      (libsource (lib "MemLib") (part "Resistor"))
    )
    (comp (ref "R36")
      (value "1 MOhm")
      (footprint "R0402")
      (description "Thick Film Resistors - SMD General Purpose Chip Resistor 0402, 1MOhms, 1%, 1/16W")
      (fields (field (name "PART NUMBER") "RC0402FR-071ML") (field (name "Comment") "Resistor"))
      (libsource (lib "MemLib") (part "Resistor"))
    )
    (comp (ref "R37")
      (value "220 Ohms")
      (footprint "R0402")
      (description "Thick Film Resistors - SMD General Purpose Chip Resistor 0402, 220Ohms, 1%, 1/16W")
      (fields (field (name "PART NUMBER") "RC0402FR-07220RL") (field (name "Comment") "Resistor"))
      (libsource (lib "MemLib") (part "Resistor"))
    )
    (comp (ref "R41")
      (value "4.7 kOhms")
      (footprint "R0402")
      (description "Thick Film Resistors - SMD General Purpose Chip Resistor 0402, 4.7kOhms, 1%, 1/16W")
      (fields (field (name "PART NUMBER") "RC0402FR-074K7L") (field (name "Comment") "Resistor"))
      (libsource (lib "MemLib") (part "Resistor"))
    )
    (comp (ref "R42")
      (value "4.7 kOhms")
      (footprint "R0402")
      (description "Thick Film Resistors - SMD General Purpose Chip Resistor 0402, 4.7kOhms, 1%, 1/16W")
      (fields (field (name "PART NUMBER") "RC0402FR-074K7L") (field (name "Comment") "Resistor"))
      (libsource (lib "MemLib") (part "Resistor"))
    )
    (comp (ref "R43")
      (value "900 kOhms")
      (footprint "R0805")
      (description "900kΩ 125mW 150V Thick Film Resistor ±1% 0805 Chip Resistor - Surface Mount RoHS")
      (fields (field (name "PART NUMBER") "CL0805FN900KPS") (field (name "Comment") "Resistor"))
      (libsource (lib "MemLib") (part "Resistor"))
    )
    (comp (ref "R44")
      (value "1 MOhm")
      (footprint "R0402")
      (description "Thick Film Resistors - SMD General Purpose Chip Resistor 0402, 1MOhms, 1%, 1/16W")
      (fields (field (name "PART NUMBER") "RC0402FR-071ML") (field (name "Comment") "Resistor"))
      (libsource (lib "MemLib") (part "Resistor"))
    )
    (comp (ref "U1")
      (value "TUSB8041IRGCR")
      (footprint "RGC0064G")
      (description "USB Interface IC TUSB8041 Four-Port U SB 3.0 Hub A 595-TU A 595-TUSB8041IRGCT")
      (fields (field (name "NOME") "TUSB8041IRGCR"))
      (libsource (lib "MemLib") (part "TUSB8041IRGCR"))
    )
    (comp (ref "U2")
      (value "TPS2553DRVR")
      (footprint "DRV0006A")
      (description "Power Switch ICs - Power Distribution Adj Crnt-Ltd Pwr- Di st Sw A 595-TPS2553DRVT")
      (fields (field (name "NOME") "TPS2553DRVR"))
      (libsource (lib "MemLib") (part "TPS2553DRVR"))
    )
    (comp (ref "U3")
      (value "TPS2553DRVR")
      (footprint "DRV0006A")
      (description "Power Switch ICs - Power Distribution Adj Crnt-Ltd Pwr- Di st Sw A 595-TPS2553DRVT")
      (fields (field (name "NOME") "TPS2553DRVR"))
      (libsource (lib "MemLib") (part "TPS2553DRVR"))
    )
    (comp (ref "U4")
      (value "TXU0101DBVR")
      (footprint "DBV0006A")
      (description "Translation - Voltage Levels Single channel fixed -direction level sh")
      (fields (field (name "NOME") "TXU0101DBVR"))
      (libsource (lib "MemLib") (part "TXU0101DBVR"))
    )
    (comp (ref "U5")
      (value "TPS2117DRLR")
      (footprint "DRL0008A")
      (description "Power Switch ICs - Power Distribution 1.6-V to 5.5-V 20-m ? 4-A low IQ power")
      (fields (field (name "NOME") "TPS2117DRLR"))
      (libsource (lib "MemLib") (part "TPS2117DRLR"))
    )
    (comp (ref "U6")
      (value "TPS2553DRVR")
      (footprint "DRV0006A")
      (description "Power Switch ICs - Power Distribution Adj Crnt-Ltd Pwr- Di st Sw A 595-TPS2553DRVT")
      (fields (field (name "NOME") "TPS2553DRVR"))
      (libsource (lib "MemLib") (part "TPS2553DRVR"))
    )
    (comp (ref "U7")
      (value "TPS2553DRVR")
      (footprint "DRV0006A")
      (description "Power Switch ICs - Power Distribution Adj Crnt-Ltd Pwr- Di st Sw A 595-TPS2553DRVT")
      (fields (field (name "NOME") "TPS2553DRVR"))
      (libsource (lib "MemLib") (part "TPS2553DRVR"))
    )
    (comp (ref "U8")
      (value "TPS74801RGWR")
      (footprint "RGW0020A")
      (description "Regulador LDO 1.5A Adj 0.8 to 3.3V")
      (fields (field (name "NOME") "TPS74801RGWR"))
      (libsource (lib "MemLib") (part "TPS74801RGWR"))
    )
    (comp (ref "U10")
      (value "TPS7A4533KTTR")
      (footprint "R-PSFM-G5")
      (description "LDO Voltage Regulators Low-Noise Fast Trans -Resp 1.5A")
      (fields (field (name "NOME") "TPS7A4533KTTR"))
      (libsource (lib "MemLib") (part "TPS7A4533KTTR"))
    )
    (comp (ref "U11")
      (value "HD3SS3220IRNHR")
      (footprint "RNH0030A")
      (description "USB Interface IC 10-Gbps USB 3.1 Type -C 2:1 mux with DRP A 595-HD3SS3220IRNHT")
      (fields (field (name "NOME") "HD3SS3220IRNHR"))
      (libsource (lib "MemLib") (part "HD3SS3220IRNHR"))
    )
    (comp (ref "Y1")
      (value "ECS-240-20-30B-TR")
      (footprint "ECS-240-20-30B-TR")
      (description "Cristais 24MHz 20pF 30 Ohms 4-SMD")
      (fields (field (name "MF") "ECS Inc."))
      (libsource (lib "MemLib") (part "ECS-240-20-30B-TR"))
    )
  )
  (nets
    (net (code "1") (name "/CC1") (class "Default")
      (node (ref "D10") (pin "2") (pinfunction "D-_2") (pintype "passive"))
      (node (ref "J1") (pin "A5") (pinfunction "CC1_A5") (pintype "bidirectional"))
      (node (ref "U11") (pin "2") (pinfunction "CC1_2") (pintype "passive"))
    )
    (net (code "2") (name "/CC2") (class "Default")
      (node (ref "D10") (pin "1") (pinfunction "D+_1") (pintype "passive"))
      (node (ref "J1") (pin "B5") (pinfunction "CC2_B5") (pintype "bidirectional"))
      (node (ref "U11") (pin "1") (pinfunction "CC2_1") (pintype "passive"))
    )
    (net (code "3") (name "/DN1_D_N") (class "Default")
      (node (ref "D1") (pin "2") (pinfunction "D-_2") (pintype "passive"))
      (node (ref "J2") (pin "2") (pinfunction "D-_2") (pintype "passive"))
      (node (ref "U1") (pin "2") (pinfunction "USB_DM_DN1_2") (pintype "passive"))
    )
    (net (code "4") (name "/DN1_D_P") (class "Default")
      (node (ref "D1") (pin "1") (pinfunction "D+_1") (pintype "passive"))
      (node (ref "J2") (pin "3") (pinfunction "D+_3") (pintype "passive"))
      (node (ref "U1") (pin "1") (pinfunction "USB_DP_DN1_1") (pintype "passive"))
    )
    (net (code "5") (name "/DN1_RX_N") (class "Default")
      (node (ref "D2") (pin "5") (pinfunction "IO4_5") (pintype "passive"))
      (node (ref "D2") (pin "6") (pinfunction "NC_6_6") (pintype "passive"))
      (node (ref "J2") (pin "5") (pinfunction "SSRX-_5") (pintype "passive"))
      (node (ref "U1") (pin "7") (pinfunction "USB_SSRXM_DN1_7") (pintype "passive"))
    )
    (net (code "6") (name "/DN1_RX_P") (class "Default")
      (node (ref "D2") (pin "4") (pinfunction "IO3_4") (pintype "passive"))
      (node (ref "D2") (pin "7") (pinfunction "NC_7_7") (pintype "passive"))
      (node (ref "J2") (pin "6") (pinfunction "SSRX+_6") (pintype "passive"))
      (node (ref "U1") (pin "6") (pinfunction "USB_SSRXP_DN1_6") (pintype "passive"))
    )
    (net (code "7") (name "/DN1_TX_N") (class "Default")
      (node (ref "C26") (pin "1") (pinfunction "1_1") (pintype "passive"))
      (node (ref "D2") (pin "2") (pinfunction "IO2_2") (pintype "passive"))
      (node (ref "D2") (pin "9") (pinfunction "NC_9_9") (pintype "passive"))
      (node (ref "U1") (pin "4") (pinfunction "USB_SSTXM_DN1_4") (pintype "passive"))
    )
    (net (code "8") (name "/DN1_TX_OUT_N") (class "Default")
      (node (ref "C26") (pin "2") (pinfunction "2_2") (pintype "passive"))
      (node (ref "J2") (pin "8") (pinfunction "SSTX-_8") (pintype "passive"))
    )
    (net (code "9") (name "/DN1_TX_OUT_P") (class "Default")
      (node (ref "C38") (pin "2") (pinfunction "2_2") (pintype "passive"))
      (node (ref "J2") (pin "9") (pinfunction "SSTX+_9") (pintype "passive"))
    )
    (net (code "10") (name "/DN1_TX_P") (class "Default")
      (node (ref "C38") (pin "1") (pinfunction "1_1") (pintype "passive"))
      (node (ref "D2") (pin "1") (pinfunction "IO1_1") (pintype "passive"))
      (node (ref "D2") (pin "10") (pinfunction "NC_10_10") (pintype "passive"))
      (node (ref "U1") (pin "3") (pinfunction "USB_SSTXP_DN1_3") (pintype "passive"))
    )
    (net (code "11") (name "/DN2_D_N") (class "Default")
      (node (ref "D3") (pin "2") (pinfunction "D-_2") (pintype "passive"))
      (node (ref "J3") (pin "2") (pinfunction "D-_2") (pintype "passive"))
      (node (ref "U1") (pin "10") (pinfunction "USB_DM_DN2_10") (pintype "passive"))
    )
    (net (code "12") (name "/DN2_D_P") (class "Default")
      (node (ref "D3") (pin "1") (pinfunction "D+_1") (pintype "passive"))
      (node (ref "J3") (pin "3") (pinfunction "D+_3") (pintype "passive"))
      (node (ref "U1") (pin "9") (pinfunction "USB_DP_DN2_9") (pintype "passive"))
    )
    (net (code "13") (name "/DN2_RX_N") (class "Default")
      (node (ref "D4") (pin "5") (pinfunction "IO4_5") (pintype "passive"))
      (node (ref "D4") (pin "6") (pinfunction "NC_6_6") (pintype "passive"))
      (node (ref "J3") (pin "5") (pinfunction "SSRX-_5") (pintype "passive"))
      (node (ref "U1") (pin "15") (pinfunction "USB_SSRXM_DN2_15") (pintype "passive"))
    )
    (net (code "14") (name "/DN2_RX_P") (class "Default")
      (node (ref "D4") (pin "4") (pinfunction "IO3_4") (pintype "passive"))
      (node (ref "D4") (pin "7") (pinfunction "NC_7_7") (pintype "passive"))
      (node (ref "J3") (pin "6") (pinfunction "SSRX+_6") (pintype "passive"))
      (node (ref "U1") (pin "14") (pinfunction "USB_SSRXP_DN2_14") (pintype "passive"))
    )
    (net (code "15") (name "/DN2_TX_N") (class "Default")
      (node (ref "C54") (pin "1") (pinfunction "1_1") (pintype "passive"))
      (node (ref "D4") (pin "2") (pinfunction "IO2_2") (pintype "passive"))
      (node (ref "D4") (pin "9") (pinfunction "NC_9_9") (pintype "passive"))
      (node (ref "U1") (pin "12") (pinfunction "USB_SSTXM_DN2_12") (pintype "passive"))
    )
    (net (code "16") (name "/DN2_TX_OUT_N") (class "Default")
      (node (ref "C54") (pin "2") (pinfunction "2_2") (pintype "passive"))
      (node (ref "J3") (pin "8") (pinfunction "SSTX-_8") (pintype "passive"))
    )
    (net (code "17") (name "/DN2_TX_OUT_P") (class "Default")
      (node (ref "C55") (pin "2") (pinfunction "2_2") (pintype "passive"))
      (node (ref "J3") (pin "9") (pinfunction "SSTX+_9") (pintype "passive"))
    )
    (net (code "18") (name "/DN2_TX_P") (class "Default")
      (node (ref "C55") (pin "1") (pinfunction "1_1") (pintype "passive"))
      (node (ref "D4") (pin "1") (pinfunction "IO1_1") (pintype "passive"))
      (node (ref "D4") (pin "10") (pinfunction "NC_10_10") (pintype "passive"))
      (node (ref "U1") (pin "11") (pinfunction "USB_SSTXP_DN2_11") (pintype "passive"))
    )
    (net (code "19") (name "/DN3_D_N") (class "Default")
      (node (ref "D5") (pin "2") (pinfunction "D-_2") (pintype "passive"))
      (node (ref "J4") (pin "2") (pinfunction "D-_2") (pintype "passive"))
      (node (ref "U1") (pin "18") (pinfunction "USB_DM_DN3_18") (pintype "passive"))
    )
    (net (code "20") (name "/DN3_D_P") (class "Default")
      (node (ref "D5") (pin "1") (pinfunction "D+_1") (pintype "passive"))
      (node (ref "J4") (pin "3") (pinfunction "D+_3") (pintype "passive"))
      (node (ref "U1") (pin "17") (pinfunction "USB_DP_DN3_17") (pintype "passive"))
    )
    (net (code "21") (name "/DN3_RX_N") (class "Default")
      (node (ref "D6") (pin "5") (pinfunction "IO4_5") (pintype "passive"))
      (node (ref "D6") (pin "6") (pinfunction "NC_6_6") (pintype "passive"))
      (node (ref "J4") (pin "5") (pinfunction "SSRX-_5") (pintype "passive"))
      (node (ref "U1") (pin "23") (pinfunction "USB_SSRXM_DN3_23") (pintype "passive"))
    )
    (net (code "22") (name "/DN3_RX_P") (class "Default")
      (node (ref "D6") (pin "4") (pinfunction "IO3_4") (pintype "passive"))
      (node (ref "D6") (pin "7") (pinfunction "NC_7_7") (pintype "passive"))
      (node (ref "J4") (pin "6") (pinfunction "SSRX+_6") (pintype "passive"))
      (node (ref "U1") (pin "22") (pinfunction "USB_SSRXP_DN3_22") (pintype "passive"))
    )
    (net (code "23") (name "/DN3_TX_N") (class "Default")
      (node (ref "C73") (pin "1") (pinfunction "1_1") (pintype "passive"))
      (node (ref "D6") (pin "2") (pinfunction "IO2_2") (pintype "passive"))
      (node (ref "D6") (pin "9") (pinfunction "NC_9_9") (pintype "passive"))
      (node (ref "U1") (pin "20") (pinfunction "USB_SSTXM_DN3_20") (pintype "passive"))
    )
    (net (code "24") (name "/DN3_TX_OUT_N") (class "Default")
      (node (ref "C73") (pin "2") (pinfunction "2_2") (pintype "passive"))
      (node (ref "J4") (pin "8") (pinfunction "SSTX-_8") (pintype "passive"))
    )
    (net (code "25") (name "/DN3_TX_OUT_P") (class "Default")
      (node (ref "C74") (pin "2") (pinfunction "2_2") (pintype "passive"))
      (node (ref "J4") (pin "9") (pinfunction "SSTX+_9") (pintype "passive"))
    )
    (net (code "26") (name "/DN3_TX_P") (class "Default")
      (node (ref "C74") (pin "1") (pinfunction "1_1") (pintype "passive"))
      (node (ref "D6") (pin "1") (pinfunction "IO1_1") (pintype "passive"))
      (node (ref "D6") (pin "10") (pinfunction "NC_10_10") (pintype "passive"))
      (node (ref "U1") (pin "19") (pinfunction "USB_SSTXP_DN3_19") (pintype "passive"))
    )
    (net (code "27") (name "/DN4_D_N") (class "Default")
      (node (ref "D7") (pin "2") (pinfunction "D-_2") (pintype "passive"))
      (node (ref "J6") (pin "2") (pinfunction "D-_2") (pintype "passive"))
      (node (ref "U1") (pin "25") (pinfunction "USB_DM_DN4_25") (pintype "passive"))
    )
    (net (code "28") (name "/DN4_D_P") (class "Default")
      (node (ref "D7") (pin "1") (pinfunction "D+_1") (pintype "passive"))
      (node (ref "J6") (pin "3") (pinfunction "D+_3") (pintype "passive"))
      (node (ref "U1") (pin "24") (pinfunction "USB_DP_DN4_24") (pintype "passive"))
    )
    (net (code "29") (name "/DN4_RX_N") (class "Default")
      (node (ref "D8") (pin "5") (pinfunction "IO4_5") (pintype "passive"))
      (node (ref "D8") (pin "6") (pinfunction "NC_6_6") (pintype "passive"))
      (node (ref "J6") (pin "5") (pinfunction "SSRX-_5") (pintype "passive"))
      (node (ref "U1") (pin "30") (pinfunction "USB_SSRXM_DN4_30") (pintype "passive"))
    )
    (net (code "30") (name "/DN4_RX_P") (class "Default")
      (node (ref "D8") (pin "4") (pinfunction "IO3_4") (pintype "passive"))
      (node (ref "D8") (pin "7") (pinfunction "NC_7_7") (pintype "passive"))
      (node (ref "J6") (pin "6") (pinfunction "SSRX+_6") (pintype "passive"))
      (node (ref "U1") (pin "29") (pinfunction "USB_SSRXP_DN4_29") (pintype "passive"))
    )
    (net (code "31") (name "/DN4_TX_N") (class "Default")
      (node (ref "C88") (pin "1") (pinfunction "1_1") (pintype "passive"))
      (node (ref "D8") (pin "2") (pinfunction "IO2_2") (pintype "passive"))
      (node (ref "D8") (pin "9") (pinfunction "NC_9_9") (pintype "passive"))
      (node (ref "U1") (pin "27") (pinfunction "USB_SSTXM_DN4_27") (pintype "passive"))
    )
    (net (code "32") (name "/DN4_TX_OUT_N") (class "Default")
      (node (ref "C88") (pin "2") (pinfunction "2_2") (pintype "passive"))
      (node (ref "J6") (pin "8") (pinfunction "SSTX-_8") (pintype "passive"))
    )
    (net (code "33") (name "/DN4_TX_OUT_P") (class "Default")
      (node (ref "C89") (pin "2") (pinfunction "2_2") (pintype "passive"))
      (node (ref "J6") (pin "9") (pinfunction "SSTX+_9") (pintype "passive"))
    )
    (net (code "34") (name "/DN4_TX_P") (class "Default")
      (node (ref "C89") (pin "1") (pinfunction "1_1") (pintype "passive"))
      (node (ref "D8") (pin "1") (pinfunction "IO1_1") (pintype "passive"))
      (node (ref "D8") (pin "10") (pinfunction "NC_10_10") (pintype "passive"))
      (node (ref "U1") (pin "26") (pinfunction "USB_SSTXP_DN4_26") (pintype "passive"))
    )
    (net (code "35") (name "/UPS_D_N") (class "Default")
      (node (ref "D9") (pin "2") (pinfunction "D-_2") (pintype "passive"))
      (node (ref "J1") (pin "A7") (pinfunction "DN1_A7") (pintype "bidirectional"))
      (node (ref "J1") (pin "B7") (pinfunction "DN2_B7") (pintype "bidirectional"))
      (node (ref "U1") (pin "54") (pinfunction "USB_DM_UP_54") (pintype "passive"))
    )
    (net (code "36") (name "/UPS_D_P") (class "Default")
      (node (ref "D9") (pin "1") (pinfunction "D+_1") (pintype "passive"))
      (node (ref "J1") (pin "A6") (pinfunction "DP1_A6") (pintype "bidirectional"))
      (node (ref "J1") (pin "B6") (pinfunction "DP2_B6") (pintype "bidirectional"))
      (node (ref "U1") (pin "53") (pinfunction "USB_DP_UP_53") (pintype "passive"))
    )
    (net (code "37") (name "/UPS_RX_1_CONNECTOR_N") (class "Default")
      (node (ref "D11") (pin "4") (pinfunction "IO3_4") (pintype "passive"))
      (node (ref "D11") (pin "7") (pinfunction "NC_7_7") (pintype "passive"))
      (node (ref "J1") (pin "B10") (pinfunction "SSRXN1_B10") (pintype "bidirectional"))
      (node (ref "U11") (pin "15") (pinfunction "RX1P_15") (pintype "passive"))
    )
    (net (code "38") (name "/UPS_RX_1_CONNECTOR_P") (class "Default")
      (node (ref "D11") (pin "5") (pinfunction "IO4_5") (pintype "passive"))
      (node (ref "D11") (pin "6") (pinfunction "NC_6_6") (pintype "passive"))
      (node (ref "J1") (pin "B11") (pinfunction "SSRXP1_B11") (pintype "bidirectional"))
      (node (ref "U11") (pin "14") (pinfunction "RX1N_14") (pintype "passive"))
    )
    (net (code "39") (name "/UPS_RX_2_CONNECTOR_N") (class "Default")
      (node (ref "D12") (pin "4") (pinfunction "IO3_4") (pintype "passive"))
      (node (ref "D12") (pin "7") (pinfunction "NC_7_7") (pintype "passive"))
      (node (ref "J1") (pin "A10") (pinfunction "SSRXN2_A10") (pintype "bidirectional"))
      (node (ref "U11") (pin "18") (pinfunction "RX2N_18") (pintype "passive"))
    )
    (net (code "40") (name "/UPS_RX_2_CONNECTOR_P") (class "Default")
      (node (ref "D12") (pin "5") (pinfunction "IO4_5") (pintype "passive"))
      (node (ref "D12") (pin "6") (pinfunction "NC_6_6") (pintype "passive"))
      (node (ref "J1") (pin "A11") (pinfunction "SSRXP2_A11") (pintype "bidirectional"))
      (node (ref "U11") (pin "19") (pinfunction "RX2P_19") (pintype "passive"))
    )
    (net (code "41") (name "/UPS_RX_N") (class "Default")
      (node (ref "U1") (pin "59") (pinfunction "USB_SSRXM_UP_59") (pintype "passive"))
      (node (ref "U11") (pin "10") (pinfunction "RXN_10") (pintype "passive"))
    )
    (net (code "42") (name "/UPS_RX_P") (class "Default")
      (node (ref "U1") (pin "58") (pinfunction "USB_SSRXP_UP_58") (pintype "passive"))
      (node (ref "U11") (pin "9") (pinfunction "RXP_9") (pintype "passive"))
    )
    (net (code "43") (name "/UPS_TX_1_CONNECTOR_IN_N") (class "Default")
      (node (ref "C97") (pin "1") (pinfunction "1_1") (pintype "passive"))
      (node (ref "D12") (pin "2") (pinfunction "IO2_2") (pintype "passive"))
      (node (ref "D12") (pin "9") (pinfunction "NC_9_9") (pintype "passive"))
      (node (ref "J1") (pin "A3") (pinfunction "SSTXN1_A3") (pintype "bidirectional"))
    )
    (net (code "44") (name "/UPS_TX_1_CONNECTOR_IN_P") (class "Default")
      (node (ref "C96") (pin "1") (pinfunction "1_1") (pintype "passive"))
      (node (ref "D12") (pin "1") (pinfunction "IO1_1") (pintype "passive"))
      (node (ref "D12") (pin "10") (pinfunction "NC_10_10") (pintype "passive"))
      (node (ref "J1") (pin "A2") (pinfunction "SSTXP1_A2") (pintype "bidirectional"))
    )
    (net (code "45") (name "/UPS_TX_1_CONNECTOR_OUT_N") (class "Default")
      (node (ref "C97") (pin "2") (pinfunction "2_2") (pintype "passive"))
      (node (ref "U11") (pin "17") (pinfunction "TX1P_17") (pintype "passive"))
    )
    (net (code "46") (name "/UPS_TX_1_CONNECTOR_OUT_P") (class "Default")
      (node (ref "C96") (pin "2") (pinfunction "2_2") (pintype "passive"))
      (node (ref "U11") (pin "16") (pinfunction "TX1N_16") (pintype "passive"))
    )
    (net (code "47") (name "/UPS_TX_2_CONNECTOR_IN_N") (class "Default")
      (node (ref "C101") (pin "1") (pinfunction "1_1") (pintype "passive"))
      (node (ref "D11") (pin "2") (pinfunction "IO2_2") (pintype "passive"))
      (node (ref "D11") (pin "9") (pinfunction "NC_9_9") (pintype "passive"))
      (node (ref "J1") (pin "B3") (pinfunction "SSTXN2_B3") (pintype "bidirectional"))
    )
    (net (code "48") (name "/UPS_TX_2_CONNECTOR_IN_P") (class "Default")
      (node (ref "C99") (pin "1") (pinfunction "1_1") (pintype "passive"))
      (node (ref "D11") (pin "1") (pinfunction "IO1_1") (pintype "passive"))
      (node (ref "D11") (pin "10") (pinfunction "NC_10_10") (pintype "passive"))
      (node (ref "J1") (pin "B2") (pinfunction "SSTXP2_B2") (pintype "bidirectional"))
    )
    (net (code "49") (name "/UPS_TX_2_CONNECTOR_OUT_N") (class "Default")
      (node (ref "C101") (pin "2") (pinfunction "2_2") (pintype "passive"))
      (node (ref "U11") (pin "20") (pinfunction "TX2N_20") (pintype "passive"))
    )
    (net (code "50") (name "/UPS_TX_2_CONNECTOR_OUT_P") (class "Default")
      (node (ref "C99") (pin "2") (pinfunction "2_2") (pintype "passive"))
      (node (ref "U11") (pin "21") (pinfunction "TX2P_21") (pintype "passive"))
    )
    (net (code "51") (name "/UPS_TX_IN_N") (class "Default")
      (node (ref "C100") (pin "1") (pinfunction "1_1") (pintype "passive"))
      (node (ref "U11") (pin "7") (pinfunction "TXN_7") (pintype "passive"))
    )
    (net (code "52") (name "/UPS_TX_IN_P") (class "Default")
      (node (ref "C98") (pin "1") (pinfunction "1_1") (pintype "passive"))
      (node (ref "U11") (pin "6") (pinfunction "TXP_6") (pintype "passive"))
    )
    (net (code "53") (name "/UPS_TX_N") (class "Default")
      (node (ref "C100") (pin "2") (pinfunction "2_2") (pintype "passive"))
      (node (ref "U1") (pin "56") (pinfunction "USB_SSTXM_UP_56") (pintype "passive"))
    )
    (net (code "54") (name "/UPS_TX_P") (class "Default")
      (node (ref "C98") (pin "2") (pinfunction "2_2") (pintype "passive"))
      (node (ref "U1") (pin "55") (pinfunction "USB_SSTXP_UP_55") (pintype "passive"))
    )
    (net (code "55") (name "1V1") (class "Default")
      (node (ref "C81") (pin "1") (pinfunction "1_1") (pintype "passive"))
      (node (ref "FB3") (pin "1") (pinfunction "1_1") (pintype "passive"))
      (node (ref "R29") (pin "2") (pinfunction "2_2") (pintype "passive"))
      (node (ref "U8") (pin "1") (pinfunction "OUT_1") (pintype "passive"))
      (node (ref "U8") (pin "18") (pinfunction "OUT_18") (pintype "passive"))
      (node (ref "U8") (pin "19") (pinfunction "OUT_19") (pintype "passive"))
      (node (ref "U8") (pin "20") (pinfunction "OUT_20") (pintype "passive"))
    )
    (net (code "56") (name "3V3") (class "Default")
      (node (ref "C20") (pin "1") (pinfunction "1_1") (pintype "passive"))
      (node (ref "C5") (pin "1") (pinfunction "1_1") (pintype "passive"))
      (node (ref "C6") (pin "1") (pinfunction "1_1") (pintype "passive"))
      (node (ref "C79") (pin "1") (pinfunction "1_1") (pintype "passive"))
      (node (ref "C80") (pin "1") (pinfunction "1_1") (pintype "passive"))
      (node (ref "FB2") (pin "1") (pinfunction "1_1") (pintype "passive"))
      (node (ref "R12") (pin "2") (pinfunction "2_2") (pintype "passive"))
      (node (ref "R13") (pin "2") (pinfunction "2_2") (pintype "passive"))
      (node (ref "R14") (pin "2") (pinfunction "2_2") (pintype "passive"))
      (node (ref "R15") (pin "2") (pinfunction "2_2") (pintype "passive"))
      (node (ref "R3") (pin "2") (pinfunction "2_2") (pintype "passive"))
      (node (ref "R41") (pin "2") (pinfunction "2_2") (pintype "passive"))
      (node (ref "R42") (pin "2") (pinfunction "2_2") (pintype "passive"))
      (node (ref "R6") (pin "2") (pinfunction "2_2") (pintype "passive"))
      (node (ref "R9") (pin "2") (pinfunction "2_2") (pintype "passive"))
      (node (ref "U10") (pin "4") (pinfunction "OUT_4") (pintype "passive"))
      (node (ref "U10") (pin "5") (pinfunction "SENSE_5") (pintype "passive"))
      (node (ref "U11") (pin "8") (pinfunction "VCC33_8") (pintype "passive"))
      (node (ref "U4") (pin "6") (pinfunction "VCCB_6") (pintype "power_in"))
      (node (ref "U8") (pin "10") (pinfunction "BIAS_10") (pintype "passive"))
      (node (ref "U8") (pin "11") (pinfunction "EN_11") (pintype "passive"))
      (node (ref "U8") (pin "5") (pinfunction "IN_5") (pintype "passive"))
      (node (ref "U8") (pin "6") (pinfunction "IN_6") (pintype "passive"))
      (node (ref "U8") (pin "7") (pinfunction "IN_7") (pintype "passive"))
      (node (ref "U8") (pin "8") (pinfunction "IN_8") (pintype "passive"))
    )
    (net (code "57") (name "5V0") (class "Default")
      (node (ref "C1") (pin "1") (pinfunction "1_1") (pintype "passive"))
      (node (ref "C21") (pin "1") (pinfunction "1_1") (pintype "passive"))
      (node (ref "C3") (pin "1") (pinfunction "1_1") (pintype "passive"))
      (node (ref "C60") (pin "1") (pinfunction "1_1") (pintype "passive"))
      (node (ref "C62") (pin "1") (pinfunction "1_1") (pintype "passive"))
      (node (ref "C69") (pin "1") (pinfunction "1_1") (pintype "passive"))
      (node (ref "C71") (pin "1") (pinfunction "1_1") (pintype "passive"))
      (node (ref "C77") (pin "1") (pinfunction "1_1") (pintype "passive"))
      (node (ref "C78") (pin "1") (pinfunction "1_1") (pintype "passive"))
      (node (ref "U10") (pin "1") (pinfunction "~{SHDN}_1") (pintype "passive"))
      (node (ref "U10") (pin "2") (pinfunction "IN_2") (pintype "passive"))
      (node (ref "U11") (pin "30") (pinfunction "VDD5_30") (pintype "passive"))
      (node (ref "U2") (pin "4") (pinfunction "EN_4") (pintype "passive"))
      (node (ref "U2") (pin "6") (pinfunction "IN_6") (pintype "passive"))
      (node (ref "U3") (pin "4") (pinfunction "EN_4") (pintype "passive"))
      (node (ref "U3") (pin "6") (pinfunction "IN_6") (pintype "passive"))
      (node (ref "U4") (pin "1") (pinfunction "VCCA_1") (pintype "power_in"))
      (node (ref "U4") (pin "5") (pinfunction "OE_5") (pintype "passive"))
      (node (ref "U5") (pin "2") (pinfunction "VOUT_2") (pintype "passive"))
      (node (ref "U5") (pin "7") (pinfunction "VOUT_7") (pintype "passive"))
      (node (ref "U6") (pin "4") (pinfunction "EN_4") (pintype "passive"))
      (node (ref "U6") (pin "6") (pinfunction "IN_6") (pintype "passive"))
      (node (ref "U7") (pin "4") (pinfunction "EN_4") (pintype "passive"))
      (node (ref "U7") (pin "6") (pinfunction "IN_6") (pintype "passive"))
    )
    (net (code "58") (name "5V0_EXT") (class "Default")
      (node (ref "C82") (pin "1") (pinfunction "1_1") (pintype "passive"))
      (node (ref "C83") (pin "1") (pinfunction "1_1") (pintype "passive"))
      (node (ref "C84") (pin "1") (pinfunction "1_1") (pintype "passive"))
      (node (ref "C85") (pin "1") (pinfunction "1_1") (pintype "passive"))
      (node (ref "C86") (pin "1") (pinfunction "1_1") (pintype "passive"))
      (node (ref "J5") (pin "A9") (pinfunction "VBUS_A9") (pintype "power_in"))
      (node (ref "J5") (pin "B9") (pinfunction "VBUS_B9") (pintype "power_in"))
      (node (ref "LED5") (pin "2") (pinfunction "2_2") (pintype "passive"))
      (node (ref "R20") (pin "2") (pinfunction "2_2") (pintype "passive"))
      (node (ref "U4") (pin "3") (pinfunction "A_3") (pintype "passive"))
      (node (ref "U5") (pin "3") (pinfunction "VIN1_3") (pintype "passive"))
      (node (ref "U5") (pin "5") (pinfunction "MODE_5") (pintype "passive"))
    )
    (net (code "59") (name "DN1_VBUS") (class "Default")
      (node (ref "C58") (pin "1") (pinfunction "1_1") (pintype "passive"))
      (node (ref "C61") (pin "1") (pinfunction "1_1") (pintype "passive"))
      (node (ref "FB1") (pin "1") (pinfunction "1_1") (pintype "passive"))
      (node (ref "U2") (pin "1") (pinfunction "OUT_1") (pintype "passive"))
    )
    (net (code "60") (name "DN2_VBUS") (class "Default")
      (node (ref "C59") (pin "1") (pinfunction "1_1") (pintype "passive"))
      (node (ref "C63") (pin "1") (pinfunction "1_1") (pintype "passive"))
      (node (ref "FB4") (pin "1") (pinfunction "1_1") (pintype "passive"))
      (node (ref "U3") (pin "1") (pinfunction "OUT_1") (pintype "passive"))
    )
    (net (code "61") (name "DN3_VBUS") (class "Default")
      (node (ref "C68") (pin "1") (pinfunction "1_1") (pintype "passive"))
      (node (ref "C72") (pin "1") (pinfunction "1_1") (pintype "passive"))
      (node (ref "FB5") (pin "1") (pinfunction "1_1") (pintype "passive"))
      (node (ref "U7") (pin "1") (pinfunction "OUT_1") (pintype "passive"))
    )
    (net (code "62") (name "DN4_VBUS") (class "Default")
      (node (ref "C67") (pin "1") (pinfunction "1_1") (pintype "passive"))
      (node (ref "C70") (pin "1") (pinfunction "1_1") (pintype "passive"))
      (node (ref "FB6") (pin "1") (pinfunction "1_1") (pintype "passive"))
      (node (ref "U6") (pin "1") (pinfunction "OUT_1") (pintype "passive"))
    )
    (net (code "63") (name "GND") (class "Default")
      (node (ref "C1") (pin "2") (pinfunction "2_2") (pintype "passive"))
      (node (ref "C10") (pin "2") (pinfunction "2_2") (pintype "passive"))
      (node (ref "C102") (pin "2") (pinfunction "2_2") (pintype "passive"))
      (node (ref "C103") (pin "2") (pinfunction "2_2") (pintype "passive"))
      (node (ref "C11") (pin "2") (pinfunction "2_2") (pintype "passive"))
      (node (ref "C12") (pin "2") (pinfunction "2_2") (pintype "passive"))
      (node (ref "C13") (pin "2") (pinfunction "2_2") (pintype "passive"))
      (node (ref "C14") (pin "2") (pinfunction "2_2") (pintype "passive"))
      (node (ref "C15") (pin "2") (pinfunction "2_2") (pintype "passive"))
      (node (ref "C16") (pin "2") (pinfunction "2_2") (pintype "passive"))
      (node (ref "C17") (pin "2") (pinfunction "2_2") (pintype "passive"))
      (node (ref "C18") (pin "2") (pinfunction "2_2") (pintype "passive"))
      (node (ref "C19") (pin "2") (pinfunction "2_2") (pintype "passive"))
      (node (ref "C2") (pin "2") (pinfunction "2_2") (pintype "passive"))
      (node (ref "C20") (pin "2") (pinfunction "2_2") (pintype "passive"))
      (node (ref "C21") (pin "2") (pinfunction "2_2") (pintype "passive"))
      (node (ref "C3") (pin "2") (pinfunction "2_2") (pintype "passive"))
      (node (ref "C30") (pin "2") (pinfunction "2_2") (pintype "passive"))
      (node (ref "C31") (pin "2") (pinfunction "2_2") (pintype "passive"))
      (node (ref "C32") (pin "2") (pinfunction "2_2") (pintype "passive"))
      (node (ref "C33") (pin "2") (pinfunction "2_2") (pintype "passive"))
      (node (ref "C34") (pin "2") (pinfunction "2_2") (pintype "passive"))
      (node (ref "C35") (pin "2") (pinfunction "2_2") (pintype "passive"))
      (node (ref "C36") (pin "2") (pinfunction "2_2") (pintype "passive"))
      (node (ref "C37") (pin "2") (pinfunction "2_2") (pintype "passive"))
      (node (ref "C39") (pin "2") (pinfunction "2_2") (pintype "passive"))
      (node (ref "C4") (pin "2") (pinfunction "2_2") (pintype "passive"))
      (node (ref "C40") (pin "2") (pinfunction "2_2") (pintype "passive"))
      (node (ref "C41") (pin "2") (pinfunction "2_2") (pintype "passive"))
      (node (ref "C42") (pin "2") (pinfunction "2_2") (pintype "passive"))
      (node (ref "C43") (pin "2") (pinfunction "2_2") (pintype "passive"))
      (node (ref "C44") (pin "2") (pinfunction "2_2") (pintype "passive"))
      (node (ref "C45") (pin "2") (pinfunction "2_2") (pintype "passive"))
      (node (ref "C46") (pin "2") (pinfunction "2_2") (pintype "passive"))
      (node (ref "C47") (pin "2") (pinfunction "2_2") (pintype "passive"))
      (node (ref "C48") (pin "2") (pinfunction "2_2") (pintype "passive"))
      (node (ref "C49") (pin "2") (pinfunction "2_2") (pintype "passive"))
      (node (ref "C5") (pin "2") (pinfunction "2_2") (pintype "passive"))
      (node (ref "C50") (pin "2") (pinfunction "2_2") (pintype "passive"))
      (node (ref "C51") (pin "1") (pinfunction "1_1") (pintype "passive"))
      (node (ref "C52") (pin "2") (pinfunction "2_2") (pintype "passive"))
      (node (ref "C53") (pin "2") (pinfunction "2_2") (pintype "passive"))
      (node (ref "C56") (pin "2") (pinfunction "2_2") (pintype "passive"))
      (node (ref "C57") (pin "2") (pinfunction "2_2") (pintype "passive"))
      (node (ref "C58") (pin "2") (pinfunction "2_2") (pintype "passive"))
      (node (ref "C59") (pin "2") (pinfunction "2_2") (pintype "passive"))
      (node (ref "C6") (pin "2") (pinfunction "2_2") (pintype "passive"))
      (node (ref "C60") (pin "2") (pinfunction "2_2") (pintype "passive"))
      (node (ref "C61") (pin "2") (pinfunction "2_2") (pintype "passive"))
      (node (ref "C62") (pin "2") (pinfunction "2_2") (pintype "passive"))
      (node (ref "C63") (pin "2") (pinfunction "2_2") (pintype "passive"))
      (node (ref "C66") (pin "2") (pinfunction "2_2") (pintype "passive"))
      (node (ref "C67") (pin "2") (pinfunction "2_2") (pintype "passive"))
      (node (ref "C68") (pin "2") (pinfunction "2_2") (pintype "passive"))
      (node (ref "C69") (pin "2") (pinfunction "2_2") (pintype "passive"))
      (node (ref "C7") (pin "2") (pinfunction "2_2") (pintype "passive"))
      (node (ref "C70") (pin "2") (pinfunction "2_2") (pintype "passive"))
      (node (ref "C71") (pin "2") (pinfunction "2_2") (pintype "passive"))
      (node (ref "C72") (pin "2") (pinfunction "2_2") (pintype "passive"))
      (node (ref "C75") (pin "2") (pinfunction "2_2") (pintype "passive"))
      (node (ref "C76") (pin "2") (pinfunction "2_2") (pintype "passive"))
      (node (ref "C77") (pin "2") (pinfunction "2_2") (pintype "passive"))
      (node (ref "C78") (pin "2") (pinfunction "2_2") (pintype "passive"))
      (node (ref "C79") (pin "2") (pinfunction "2_2") (pintype "passive"))
      (node (ref "C8") (pin "2") (pinfunction "2_2") (pintype "passive"))
      (node (ref "C80") (pin "2") (pinfunction "2_2") (pintype "passive"))
      (node (ref "C81") (pin "2") (pinfunction "2_2") (pintype "passive"))
      (node (ref "C82") (pin "2") (pinfunction "2_2") (pintype "passive"))
      (node (ref "C83") (pin "2") (pinfunction "2_2") (pintype "passive"))
      (node (ref "C84") (pin "2") (pinfunction "2_2") (pintype "passive"))
      (node (ref "C85") (pin "2") (pinfunction "2_2") (pintype "passive"))
      (node (ref "C86") (pin "2") (pinfunction "2_2") (pintype "passive"))
      (node (ref "C87") (pin "2") (pinfunction "2_2") (pintype "passive"))
      (node (ref "C9") (pin "2") (pinfunction "2_2") (pintype "passive"))
      (node (ref "C90") (pin "2") (pinfunction "2_2") (pintype "passive"))
      (node (ref "C91") (pin "2") (pinfunction "2_2") (pintype "passive"))
      (node (ref "C92") (pin "2") (pinfunction "2_2") (pintype "passive"))
      (node (ref "C93") (pin "2") (pinfunction "2_2") (pintype "passive"))
      (node (ref "C94") (pin "2") (pinfunction "2_2") (pintype "passive"))
      (node (ref "C95") (pin "2") (pinfunction "2_2") (pintype "passive"))
      (node (ref "D1") (pin "3") (pinfunction "GND_3") (pintype "power_in"))
      (node (ref "D10") (pin "3") (pinfunction "GND_3") (pintype "power_in"))
      (node (ref "D11") (pin "3") (pinfunction "GND_3_3") (pintype "power_in"))
      (node (ref "D11") (pin "8") (pinfunction "GND_8_8") (pintype "power_in"))
      (node (ref "D12") (pin "3") (pinfunction "GND_3_3") (pintype "power_in"))
      (node (ref "D12") (pin "8") (pinfunction "GND_8_8") (pintype "power_in"))
      (node (ref "D2") (pin "3") (pinfunction "GND_3_3") (pintype "power_in"))
      (node (ref "D2") (pin "8") (pinfunction "GND_8_8") (pintype "power_in"))
      (node (ref "D3") (pin "3") (pinfunction "GND_3") (pintype "power_in"))
      (node (ref "D4") (pin "3") (pinfunction "GND_3_3") (pintype "power_in"))
      (node (ref "D4") (pin "8") (pinfunction "GND_8_8") (pintype "power_in"))
      (node (ref "D5") (pin "3") (pinfunction "GND_3") (pintype "power_in"))
      (node (ref "D6") (pin "3") (pinfunction "GND_3_3") (pintype "power_in"))
      (node (ref "D6") (pin "8") (pinfunction "GND_8_8") (pintype "power_in"))
      (node (ref "D7") (pin "3") (pinfunction "GND_3") (pintype "power_in"))
      (node (ref "D8") (pin "3") (pinfunction "GND_3_3") (pintype "power_in"))
      (node (ref "D8") (pin "8") (pinfunction "GND_8_8") (pintype "power_in"))
      (node (ref "D9") (pin "3") (pinfunction "GND_3") (pintype "power_in"))
      (node (ref "J1") (pin "A1") (pinfunction "GND_A_A1") (pintype "power_in"))
      (node (ref "J1") (pin "A12") (pinfunction "GND_A_A12") (pintype "power_in"))
      (node (ref "J1") (pin "B1") (pinfunction "GND_B_B1") (pintype "power_in"))
      (node (ref "J1") (pin "B12") (pinfunction "GND_B_B12") (pintype "power_in"))
      (node (ref "J2") (pin "4") (pinfunction "GND_4") (pintype "power_in"))
      (node (ref "J2") (pin "7") (pinfunction "GND_7") (pintype "power_in"))
      (node (ref "J3") (pin "4") (pinfunction "GND_4") (pintype "power_in"))
      (node (ref "J3") (pin "7") (pinfunction "GND_7") (pintype "power_in"))
      (node (ref "J4") (pin "4") (pinfunction "GND_4") (pintype "power_in"))
      (node (ref "J5") (pin "A12") (pinfunction "GND_A12") (pintype "power_in"))
      (node (ref "J5") (pin "B12") (pinfunction "GND_B12") (pintype "power_in"))
      (node (ref "J5") (pin "SH") (pinfunction "SHIELD_SH") (pintype "passive"))
      (node (ref "J6") (pin "4") (pinfunction "GND_4") (pintype "power_in"))
      (node (ref "J6") (pin "7") (pinfunction "GND_7") (pintype "power_in"))
      (node (ref "R10") (pin "1") (pinfunction "1_1") (pintype "passive"))
      (node (ref "R11") (pin "1") (pinfunction "1_1") (pintype "passive"))
      (node (ref "R16") (pin "1") (pinfunction "1_1") (pintype "passive"))
      (node (ref "R17") (pin "1") (pinfunction "1_1") (pintype "passive"))
      (node (ref "R18") (pin "1") (pinfunction "1_1") (pintype "passive"))
      (node (ref "R19") (pin "1") (pinfunction "1_1") (pintype "passive"))
      (node (ref "R2") (pin "1") (pinfunction "1_1") (pintype "passive"))
      (node (ref "R22") (pin "1") (pinfunction "1_1") (pintype "passive"))
      (node (ref "R23") (pin "1") (pinfunction "1_1") (pintype "passive"))
      (node (ref "R24") (pin "1") (pinfunction "1_1") (pintype "passive"))
      (node (ref "R25") (pin "1") (pinfunction "1_1") (pintype "passive"))
      (node (ref "R27") (pin "1") (pinfunction "1_1") (pintype "passive"))
      (node (ref "R28") (pin "1") (pinfunction "1_1") (pintype "passive"))
      (node (ref "R30") (pin "1") (pinfunction "1_1") (pintype "passive"))
      (node (ref "R31") (pin "1") (pinfunction "1_1") (pintype "passive"))
      (node (ref "R32") (pin "1") (pinfunction "1_1") (pintype "passive"))
      (node (ref "R33") (pin "1") (pinfunction "1_1") (pintype "passive"))
      (node (ref "R34") (pin "1") (pinfunction "1_1") (pintype "passive"))
      (node (ref "R35") (pin "1") (pinfunction "1_1") (pintype "passive"))
      (node (ref "R36") (pin "1") (pinfunction "1_1") (pintype "passive"))
      (node (ref "R37") (pin "1") (pinfunction "1_1") (pintype "passive"))
      (node (ref "R4") (pin "1") (pinfunction "1_1") (pintype "passive"))
      (node (ref "R44") (pin "2") (pinfunction "2_2") (pintype "passive"))
      (node (ref "R7") (pin "1") (pinfunction "1_1") (pintype "passive"))
      (node (ref "R8") (pin "1") (pinfunction "1_1") (pintype "passive"))
      (node (ref "U1") (pin "65") (pinfunction "EP_65") (pintype "passive"))
      (node (ref "U10") (pin "3") (pinfunction "GND_3") (pintype "power_in"))
      (node (ref "U10") (pin "6") (pinfunction "EP_6") (pintype "power_in"))
      (node (ref "U11") (pin "12") (pinfunction "ENN_MUX_12") (pintype "passive"))
      (node (ref "U11") (pin "13") (pinfunction "GND_1_13") (pintype "passive"))
      (node (ref "U11") (pin "28") (pinfunction "GND_2_28") (pintype "passive"))
      (node (ref "U11") (pin "29") (pinfunction "ENN_CC_29") (pintype "passive"))
      (node (ref "U11") (pin "31") (pinfunction "EP_31") (pintype "passive"))
      (node (ref "U2") (pin "5") (pinfunction "GND_5") (pintype "power_in"))
      (node (ref "U2") (pin "7") (pinfunction "EP_7") (pintype "passive"))
      (node (ref "U3") (pin "5") (pinfunction "GND_5") (pintype "power_in"))
      (node (ref "U3") (pin "7") (pinfunction "EP_7") (pintype "passive"))
      (node (ref "U4") (pin "2") (pinfunction "GND_2") (pintype "power_in"))
      (node (ref "U5") (pin "1") (pinfunction "GND_1") (pintype "power_in"))
      (node (ref "U6") (pin "5") (pinfunction "GND_5") (pintype "power_in"))
      (node (ref "U6") (pin "7") (pinfunction "EP_7") (pintype "passive"))
      (node (ref "U7") (pin "5") (pinfunction "GND_5") (pintype "power_in"))
      (node (ref "U7") (pin "7") (pinfunction "EP_7") (pintype "passive"))
      (node (ref "U8") (pin "12") (pinfunction "GND_12") (pintype "passive"))
      (node (ref "U8") (pin "13") (pinfunction "NC_13") (pintype "passive"))
      (node (ref "U8") (pin "14") (pinfunction "NC_14") (pintype "passive"))
      (node (ref "U8") (pin "17") (pinfunction "NC_17") (pintype "passive"))
      (node (ref "U8") (pin "2") (pinfunction "NC_2") (pintype "passive"))
      (node (ref "U8") (pin "21") (pinfunction "GND_21") (pintype "passive"))
      (node (ref "U8") (pin "3") (pinfunction "NC_3") (pintype "passive"))
      (node (ref "U8") (pin "4") (pinfunction "NC_4") (pintype "passive"))
      (node (ref "Y1") (pin "2") (pinfunction "2_2") (pintype "passive"))
      (node (ref "Y1") (pin "4") (pinfunction "4_4") (pintype "passive"))
    )
    (net (code "64") (name "Net-(J2-VBUS)") (class "Default")
      (node (ref "C4") (pin "1") (pinfunction "1_1") (pintype "passive"))
      (node (ref "FB1") (pin "2") (pinfunction "2_2") (pintype "passive"))
      (node (ref "J2") (pin "1") (pinfunction "VBUS_1") (pintype "power_in"))
      (node (ref "LED1") (pin "2") (pinfunction "2_2") (pintype "passive"))
    )
    (net (code "65") (name "Net-(J3-VBUS)") (class "Default")
      (node (ref "C53") (pin "1") (pinfunction "1_1") (pintype "passive"))
      (node (ref "FB4") (pin "2") (pinfunction "2_2") (pintype "passive"))
      (node (ref "J3") (pin "1") (pinfunction "VBUS_1") (pintype "power_in"))
      (node (ref "LED2") (pin "2") (pinfunction "2_2") (pintype "passive"))
    )
    (net (code "66") (name "Net-(J4-VBUS)") (class "Default")
      (node (ref "C66") (pin "1") (pinfunction "1_1") (pintype "passive"))
      (node (ref "FB5") (pin "2") (pinfunction "2_2") (pintype "passive"))
      (node (ref "J4") (pin "1") (pinfunction "VBUS_1") (pintype "power_in"))
      (node (ref "LED3") (pin "2") (pinfunction "2_2") (pintype "passive"))
    )
    (net (code "67") (name "Net-(J5-CC1)") (class "Default")
      (node (ref "J5") (pin "A5") (pinfunction "CC1_A5") (pintype "bidirectional"))
      (node (ref "R23") (pin "2") (pinfunction "2_2") (pintype "passive"))
    )
    (net (code "68") (name "Net-(J5-CC2)") (class "Default")
      (node (ref "J5") (pin "B5") (pinfunction "CC2_B5") (pintype "bidirectional"))
      (node (ref "R22") (pin "2") (pinfunction "2_2") (pintype "passive"))
    )
    (net (code "69") (name "Net-(J6-VBUS)") (class "Default")
      (node (ref "C87") (pin "1") (pinfunction "1_1") (pintype "passive"))
      (node (ref "FB6") (pin "2") (pinfunction "2_2") (pintype "passive"))
      (node (ref "J6") (pin "1") (pinfunction "VBUS_1") (pintype "power_in"))
      (node (ref "LED4") (pin "2") (pinfunction "2_2") (pintype "passive"))
    )
    (net (code "70") (name "Net-(LED1-Pad1)") (class "Default")
      (node (ref "LED1") (pin "1") (pinfunction "1_1") (pintype "passive"))
      (node (ref "R30") (pin "2") (pinfunction "2_2") (pintype "passive"))
    )
    (net (code "71") (name "Net-(LED2-Pad1)") (class "Default")
      (node (ref "LED2") (pin "1") (pinfunction "1_1") (pintype "passive"))
      (node (ref "R31") (pin "2") (pinfunction "2_2") (pintype "passive"))
    )
    (net (code "72") (name "Net-(LED3-Pad1)") (class "Default")
      (node (ref "LED3") (pin "1") (pinfunction "1_1") (pintype "passive"))
      (node (ref "R33") (pin "2") (pinfunction "2_2") (pintype "passive"))
    )
    (net (code "73") (name "Net-(LED4-Pad1)") (class "Default")
      (node (ref "LED4") (pin "1") (pinfunction "1_1") (pintype "passive"))
      (node (ref "R34") (pin "2") (pinfunction "2_2") (pintype "passive"))
    )
    (net (code "74") (name "Net-(LED5-Pad1)") (class "Default")
      (node (ref "LED5") (pin "1") (pinfunction "1_1") (pintype "passive"))
      (node (ref "R35") (pin "2") (pinfunction "2_2") (pintype "passive"))
    )
    (net (code "75") (name "Net-(LED6-Pad1)") (class "Default")
      (node (ref "LED6") (pin "1") (pinfunction "1_1") (pintype "passive"))
      (node (ref "R37") (pin "2") (pinfunction "2_2") (pintype "passive"))
    )
    (net (code "76") (name "Net-(R20-Pad1)") (class "Default")
      (node (ref "R20") (pin "1") (pinfunction "1_1") (pintype "passive"))
      (node (ref "R21") (pin "2") (pinfunction "2_2") (pintype "passive"))
    )
    (net (code "77") (name "Net-(R21-Pad1)") (class "Default")
      (node (ref "R21") (pin "1") (pinfunction "1_1") (pintype "passive"))
      (node (ref "R26") (pin "2") (pinfunction "2_2") (pintype "passive"))
    )
    (net (code "78") (name "Net-(U1-AUTOENZ{slash}HS_SUSPEND)") (class "Default")
      (node (ref "R6") (pin "1") (pinfunction "1_1") (pintype "passive"))
      (node (ref "U1") (pin "45") (pinfunction "AUTOENZ/HS_SUSPEND_45") (pintype "passive"))
    )
    (net (code "79") (name "Net-(U1-FULLPWRMGMTZ{slash}SMBA1{slash}SS_UP)") (class "Default")
      (node (ref "R10") (pin "2") (pinfunction "2_2") (pintype "passive"))
      (node (ref "U1") (pin "40") (pinfunction "FULLPWRMGMTZ/SMBA1/SS_UP_40") (pintype "passive"))
    )
    (net (code "80") (name "Net-(U1-GANGED{slash}SMBA2{slash}HS_UP)") (class "Default")
      (node (ref "R11") (pin "2") (pinfunction "2_2") (pintype "passive"))
      (node (ref "U1") (pin "42") (pinfunction "GANGED/SMBA2/HS_UP_42") (pintype "passive"))
    )
    (net (code "81") (name "Net-(U1-GRSTZ)") (class "Default")
      (node (ref "C52") (pin "1") (pinfunction "1_1") (pintype "passive"))
      (node (ref "U1") (pin "50") (pinfunction "GRSTZ_50") (pintype "passive"))
    )
    (net (code "82") (name "Net-(U1-OVERCUR1Z)") (class "Default")
      (node (ref "R12") (pin "1") (pinfunction "1_1") (pintype "passive"))
      (node (ref "U1") (pin "46") (pinfunction "OVERCUR1Z_46") (pintype "passive"))
      (node (ref "U2") (pin "3") (pinfunction "~{FAULT}_3") (pintype "passive"))
    )
    (net (code "83") (name "Net-(U1-OVERCUR2Z)") (class "Default")
      (node (ref "R13") (pin "1") (pinfunction "1_1") (pintype "passive"))
      (node (ref "U1") (pin "47") (pinfunction "OVERCUR2Z_47") (pintype "passive"))
      (node (ref "U3") (pin "3") (pinfunction "~{FAULT}_3") (pintype "passive"))
    )
    (net (code "84") (name "Net-(U1-OVERCUR3Z)") (class "Default")
      (node (ref "R14") (pin "1") (pinfunction "1_1") (pintype "passive"))
      (node (ref "U1") (pin "44") (pinfunction "OVERCUR3Z_44") (pintype "passive"))
      (node (ref "U7") (pin "3") (pinfunction "~{FAULT}_3") (pintype "passive"))
    )
    (net (code "85") (name "Net-(U1-OVERCUR4Z)") (class "Default")
      (node (ref "R15") (pin "1") (pinfunction "1_1") (pintype "passive"))
      (node (ref "U1") (pin "43") (pinfunction "OVERCUR4Z_43") (pintype "passive"))
      (node (ref "U6") (pin "3") (pinfunction "~{FAULT}_3") (pintype "passive"))
    )
    (net (code "86") (name "Net-(U1-PWRCTL1{slash}BATEN1)") (class "Default")
      (node (ref "U1") (pin "32") (pinfunction "PWRCTL4/BATEN4_32") (pintype "passive"))
      (node (ref "U1") (pin "33") (pinfunction "PWRCTL3/BATEN3_33") (pintype "passive"))
      (node (ref "U1") (pin "35") (pinfunction "PWRCTL2/BATEN2_35") (pintype "passive"))
      (node (ref "U1") (pin "36") (pinfunction "PWRCTL1/BATEN1_36") (pintype "passive"))
      (node (ref "U4") (pin "4") (pinfunction "BY_4") (pintype "passive"))
    )
    (net (code "87") (name "Net-(U1-TEST)") (class "Default")
      (node (ref "R8") (pin "2") (pinfunction "2_2") (pintype "passive"))
      (node (ref "U1") (pin "49") (pinfunction "TEST_49") (pintype "passive"))
    )
    (net (code "88") (name "Net-(U1-USB_R1)") (class "Default")
      (node (ref "R7") (pin "2") (pinfunction "2_2") (pintype "passive"))
      (node (ref "U1") (pin "64") (pinfunction "USB_R1_64") (pintype "passive"))
    )
    (net (code "89") (name "Net-(U1-USB_VBUS)") (class "Default")
      (node (ref "R1") (pin "1") (pinfunction "1_1") (pintype "passive"))
      (node (ref "R2") (pin "2") (pinfunction "2_2") (pintype "passive"))
      (node (ref "U1") (pin "48") (pinfunction "USB_VBUS_48") (pintype "passive"))
    )
    (net (code "90") (name "Net-(U1-VDD33_1)") (class "Default")
      (node (ref "C10") (pin "1") (pinfunction "1_1") (pintype "passive"))
      (node (ref "C11") (pin "1") (pinfunction "1_1") (pintype "passive"))
      (node (ref "C12") (pin "1") (pinfunction "1_1") (pintype "passive"))
      (node (ref "C13") (pin "1") (pinfunction "1_1") (pintype "passive"))
      (node (ref "C14") (pin "1") (pinfunction "1_1") (pintype "passive"))
      (node (ref "C15") (pin "1") (pinfunction "1_1") (pintype "passive"))
      (node (ref "C16") (pin "1") (pinfunction "1_1") (pintype "passive"))
      (node (ref "C17") (pin "1") (pinfunction "1_1") (pintype "passive"))
      (node (ref "C18") (pin "1") (pinfunction "1_1") (pintype "passive"))
      (node (ref "C19") (pin "1") (pinfunction "1_1") (pintype "passive"))
      (node (ref "C7") (pin "1") (pinfunction "1_1") (pintype "passive"))
      (node (ref "C8") (pin "1") (pinfunction "1_1") (pintype "passive"))
      (node (ref "C9") (pin "1") (pinfunction "1_1") (pintype "passive"))
      (node (ref "FB2") (pin "2") (pinfunction "2_2") (pintype "passive"))
      (node (ref "U1") (pin "16") (pinfunction "VDD33_1_16") (pintype "passive"))
      (node (ref "U1") (pin "34") (pinfunction "VDD33_2_34") (pintype "passive"))
      (node (ref "U1") (pin "52") (pinfunction "VDD33_3_52") (pintype "passive"))
      (node (ref "U1") (pin "63") (pinfunction "VDD33_4_63") (pintype "passive"))
    )
    (net (code "91") (name "Net-(U1-VDD_1)") (class "Default")
      (node (ref "C30") (pin "1") (pinfunction "1_1") (pintype "passive"))
      (node (ref "C31") (pin "1") (pinfunction "1_1") (pintype "passive"))
      (node (ref "C32") (pin "1") (pinfunction "1_1") (pintype "passive"))
      (node (ref "C33") (pin "1") (pinfunction "1_1") (pintype "passive"))
      (node (ref "C34") (pin "1") (pinfunction "1_1") (pintype "passive"))
      (node (ref "C35") (pin "1") (pinfunction "1_1") (pintype "passive"))
      (node (ref "C36") (pin "1") (pinfunction "1_1") (pintype "passive"))
      (node (ref "C37") (pin "1") (pinfunction "1_1") (pintype "passive"))
      (node (ref "C39") (pin "1") (pinfunction "1_1") (pintype "passive"))
      (node (ref "C40") (pin "1") (pinfunction "1_1") (pintype "passive"))
      (node (ref "C41") (pin "1") (pinfunction "1_1") (pintype "passive"))
      (node (ref "C42") (pin "1") (pinfunction "1_1") (pintype "passive"))
      (node (ref "C43") (pin "1") (pinfunction "1_1") (pintype "passive"))
      (node (ref "C44") (pin "1") (pinfunction "1_1") (pintype "passive"))
      (node (ref "C45") (pin "1") (pinfunction "1_1") (pintype "passive"))
      (node (ref "C46") (pin "1") (pinfunction "1_1") (pintype "passive"))
      (node (ref "C47") (pin "1") (pinfunction "1_1") (pintype "passive"))
      (node (ref "FB3") (pin "2") (pinfunction "2_2") (pintype "passive"))
      (node (ref "U1") (pin "13") (pinfunction "VDD_3_13") (pintype "passive"))
      (node (ref "U1") (pin "21") (pinfunction "VDD_4_21") (pintype "passive"))
      (node (ref "U1") (pin "28") (pinfunction "VDD_5_28") (pintype "passive"))
      (node (ref "U1") (pin "31") (pinfunction "VDD_6_31") (pintype "passive"))
      (node (ref "U1") (pin "5") (pinfunction "VDD_1_5") (pintype "passive"))
      (node (ref "U1") (pin "51") (pinfunction "VDD_7_51") (pintype "passive"))
      (node (ref "U1") (pin "57") (pinfunction "VDD_8_57") (pintype "passive"))
      (node (ref "U1") (pin "8") (pinfunction "VDD_2_8") (pintype "passive"))
    )
    (net (code "92") (name "Net-(U1-XI)") (class "Default")
      (node (ref "C51") (pin "2") (pinfunction "2_2") (pintype "passive"))
      (node (ref "R5") (pin "1") (pinfunction "1_1") (pintype "passive"))
      (node (ref "U1") (pin "62") (pinfunction "XI_62") (pintype "passive"))
      (node (ref "Y1") (pin "3") (pinfunction "3_3") (pintype "passive"))
    )
    (net (code "93") (name "Net-(U1-XO)") (class "Default")
      (node (ref "C48") (pin "1") (pinfunction "1_1") (pintype "passive"))
      (node (ref "R5") (pin "2") (pinfunction "2_2") (pintype "passive"))
      (node (ref "U1") (pin "61") (pinfunction "XO_61") (pintype "passive"))
      (node (ref "Y1") (pin "1") (pinfunction "1_1") (pintype "passive"))
    )
    (net (code "94") (name "Net-(U2-ILIM)") (class "Default")
      (node (ref "R17") (pin "2") (pinfunction "2_2") (pintype "passive"))
      (node (ref "U2") (pin "2") (pinfunction "ILIM_2") (pintype "passive"))
    )
    (net (code "95") (name "Net-(U3-ILIM)") (class "Default")
      (node (ref "R18") (pin "2") (pinfunction "2_2") (pintype "passive"))
      (node (ref "U3") (pin "2") (pinfunction "ILIM_2") (pintype "passive"))
    )
    (net (code "96") (name "Net-(U5-PR1)") (class "Default")
      (node (ref "R26") (pin "1") (pinfunction "1_1") (pintype "passive"))
      (node (ref "R27") (pin "2") (pinfunction "2_2") (pintype "passive"))
      (node (ref "U5") (pin "4") (pinfunction "PR1_4") (pintype "passive"))
    )
    (net (code "97") (name "Net-(U6-ILIM)") (class "Default")
      (node (ref "R24") (pin "2") (pinfunction "2_2") (pintype "passive"))
      (node (ref "U6") (pin "2") (pinfunction "ILIM_2") (pintype "passive"))
    )
    (net (code "98") (name "Net-(U7-ILIM)") (class "Default")
      (node (ref "R25") (pin "2") (pinfunction "2_2") (pintype "passive"))
      (node (ref "U7") (pin "2") (pinfunction "ILIM_2") (pintype "passive"))
    )
    (net (code "99") (name "Net-(U8-FB)") (class "Default")
      (node (ref "R29") (pin "1") (pinfunction "1_1") (pintype "passive"))
      (node (ref "R32") (pin "2") (pinfunction "2_2") (pintype "passive"))
      (node (ref "U8") (pin "16") (pinfunction "FB_16") (pintype "passive"))
    )
    (net (code "100") (name "Net-(U11-DIR)") (class "Default")
      (node (ref "R3") (pin "1") (pinfunction "1_1") (pintype "passive"))
      (node (ref "U11") (pin "11") (pinfunction "DIR_11") (pintype "passive"))
    )
    (net (code "101") (name "Net-(U11-INT_N{slash}OUT3)") (class "Default")
      (node (ref "R9") (pin "1") (pinfunction "1_1") (pintype "passive"))
      (node (ref "U11") (pin "23") (pinfunction "INT_N/OUT3_23") (pintype "passive"))
    )
    (net (code "102") (name "Net-(U11-PORT)") (class "Default")
      (node (ref "R19") (pin "2") (pinfunction "2_2") (pintype "passive"))
      (node (ref "U11") (pin "4") (pinfunction "PORT_4") (pintype "passive"))
    )
    (net (code "103") (name "Net-(U11-SCL{slash}OUT2)") (class "Default")
      (node (ref "R42") (pin "1") (pinfunction "1_1") (pintype "passive"))
      (node (ref "U11") (pin "26") (pinfunction "SCL/OUT2_26") (pintype "passive"))
    )
    (net (code "104") (name "Net-(U11-SDA{slash}OUT1)") (class "Default")
      (node (ref "R41") (pin "1") (pinfunction "1_1") (pintype "passive"))
      (node (ref "U11") (pin "25") (pinfunction "SDA/OUT1_25") (pintype "passive"))
    )
    (net (code "105") (name "Net-(U11-VBUS_DET)") (class "Default")
      (node (ref "R43") (pin "2") (pinfunction "2_2") (pintype "passive"))
      (node (ref "U11") (pin "5") (pinfunction "VBUS_DET_5") (pintype "passive"))
    )
    (net (code "106") (name "SGND") (class "Default")
      (node (ref "C102") (pin "1") (pinfunction "1_1") (pintype "passive"))
      (node (ref "C103") (pin "1") (pinfunction "1_1") (pintype "passive"))
      (node (ref "C49") (pin "1") (pinfunction "1_1") (pintype "passive"))
      (node (ref "C50") (pin "1") (pinfunction "1_1") (pintype "passive"))
      (node (ref "C56") (pin "1") (pinfunction "1_1") (pintype "passive"))
      (node (ref "C57") (pin "1") (pinfunction "1_1") (pintype "passive"))
      (node (ref "C75") (pin "1") (pinfunction "1_1") (pintype "passive"))
      (node (ref "C76") (pin "1") (pinfunction "1_1") (pintype "passive"))
      (node (ref "C90") (pin "1") (pinfunction "1_1") (pintype "passive"))
      (node (ref "C91") (pin "1") (pinfunction "1_1") (pintype "passive"))
      (node (ref "J1") (pin "SH") (pinfunction "SHIELD_SH") (pintype "passive"))
      (node (ref "J2") (pin "SH") (pinfunction "SHIELD_SH") (pintype "passive"))
      (node (ref "J3") (pin "SH") (pinfunction "SHIELD_SH") (pintype "passive"))
      (node (ref "J4") (pin "SH") (pinfunction "SHIELD_SH") (pintype "passive"))
      (node (ref "J6") (pin "SH") (pinfunction "SHIELD_SH") (pintype "passive"))
      (node (ref "R16") (pin "2") (pinfunction "2_2") (pintype "passive"))
      (node (ref "R28") (pin "2") (pinfunction "2_2") (pintype "passive"))
      (node (ref "R36") (pin "2") (pinfunction "2_2") (pintype "passive"))
      (node (ref "R4") (pin "2") (pinfunction "2_2") (pintype "passive"))
      (node (ref "R44") (pin "1") (pinfunction "1_1") (pintype "passive"))
    )
    (net (code "107") (name "UPS_VBUS") (class "Default")
      (node (ref "C2") (pin "1") (pinfunction "1_1") (pintype "passive"))
      (node (ref "C92") (pin "1") (pinfunction "1_1") (pintype "passive"))
      (node (ref "C93") (pin "1") (pinfunction "1_1") (pintype "passive"))
      (node (ref "C94") (pin "1") (pinfunction "1_1") (pintype "passive"))
      (node (ref "C95") (pin "1") (pinfunction "1_1") (pintype "passive"))
      (node (ref "J1") (pin "A4") (pinfunction "VBUS_A_A4") (pintype "power_in"))
      (node (ref "J1") (pin "A9") (pinfunction "VBUS_A_A9") (pintype "power_in"))
      (node (ref "J1") (pin "B4") (pinfunction "VBUS_B_B4") (pintype "power_in"))
      (node (ref "J1") (pin "B9") (pinfunction "VBUS_B_B9") (pintype "power_in"))
      (node (ref "LED6") (pin "2") (pinfunction "2_2") (pintype "passive"))
      (node (ref "R1") (pin "2") (pinfunction "2_2") (pintype "passive"))
      (node (ref "R43") (pin "1") (pinfunction "1_1") (pintype "passive"))
      (node (ref "U5") (pin "6") (pinfunction "VIN2_6") (pintype "passive"))
    )
    (net (code "108") (name "unconnected-(J1-SBU1-PadA8)") (class "Default")
      (node (ref "J1") (pin "A8") (pinfunction "SBU1_A8") (pintype "bidirectional+no_connect"))
    )
    (net (code "109") (name "unconnected-(J1-SBU2-PadB8)") (class "Default")
      (node (ref "J1") (pin "B8") (pinfunction "SBU2_B8") (pintype "bidirectional+no_connect"))
    )
    (net (code "110") (name "unconnected-(J4-GND-Pad7)") (class "Default")
      (node (ref "J4") (pin "7") (pinfunction "GND_7") (pintype "power_in"))
    )
    (net (code "111") (name "unconnected-(U1-NC-Pad60)") (class "Default")
      (node (ref "U1") (pin "60") (pinfunction "NC_60") (pintype "passive+no_connect"))
    )
    (net (code "112") (name "unconnected-(U1-PWRCTL_POL-Pad41)") (class "Default")
      (node (ref "U1") (pin "41") (pinfunction "PWRCTL_POL_41") (pintype "passive+no_connect"))
    )
    (net (code "113") (name "unconnected-(U1-SCL{slash}SMBCLK-Pad38)") (class "Default")
      (node (ref "U1") (pin "38") (pinfunction "SCL/SMBCLK_38") (pintype "passive+no_connect"))
    )
    (net (code "114") (name "unconnected-(U1-SDA{slash}SMBDAT-Pad37)") (class "Default")
      (node (ref "U1") (pin "37") (pinfunction "SDA/SMBDAT_37") (pintype "passive+no_connect"))
    )
    (net (code "115") (name "unconnected-(U1-SMBUSZ{slash}SS_SUSPEND-Pad39)") (class "Default")
      (node (ref "U1") (pin "39") (pinfunction "SMBUSZ/SS_SUSPEND_39") (pintype "passive+no_connect"))
    )
    (net (code "116") (name "unconnected-(U5-ST-Pad8)") (class "Default")
      (node (ref "U5") (pin "8") (pinfunction "ST_8") (pintype "passive+no_connect"))
    )
    (net (code "117") (name "unconnected-(U8-PG-Pad9)") (class "Default")
      (node (ref "U8") (pin "9") (pinfunction "PG_9") (pintype "passive+no_connect"))
    )
    (net (code "118") (name "unconnected-(U8-SS-Pad15)") (class "Default")
      (node (ref "U8") (pin "15") (pinfunction "SS_15") (pintype "passive+no_connect"))
    )
    (net (code "119") (name "unconnected-(U11-ADDR-Pad22)") (class "Default")
      (node (ref "U11") (pin "22") (pinfunction "ADDR_22") (pintype "passive+no_connect"))
    )
    (net (code "120") (name "unconnected-(U11-CURRENT_MODE-Pad3)") (class "Default")
      (node (ref "U11") (pin "3") (pinfunction "CURRENT_MODE_3") (pintype "passive+no_connect"))
    )
    (net (code "121") (name "unconnected-(U11-ID-Pad27)") (class "Default")
      (node (ref "U11") (pin "27") (pinfunction "ID_27") (pintype "passive+no_connect"))
    )
    (net (code "122") (name "unconnected-(U11-VCONN_FAULT_N-Pad24)") (class "Default")
      (node (ref "U11") (pin "24") (pinfunction "VCONN_FAULT_N_24") (pintype "passive+no_connect"))
    )
  )
)
